# 04_-_CPU_-_DDR3_DDR3_MEM.net
KiCad netlist of a schematic drawn in Altium Designer
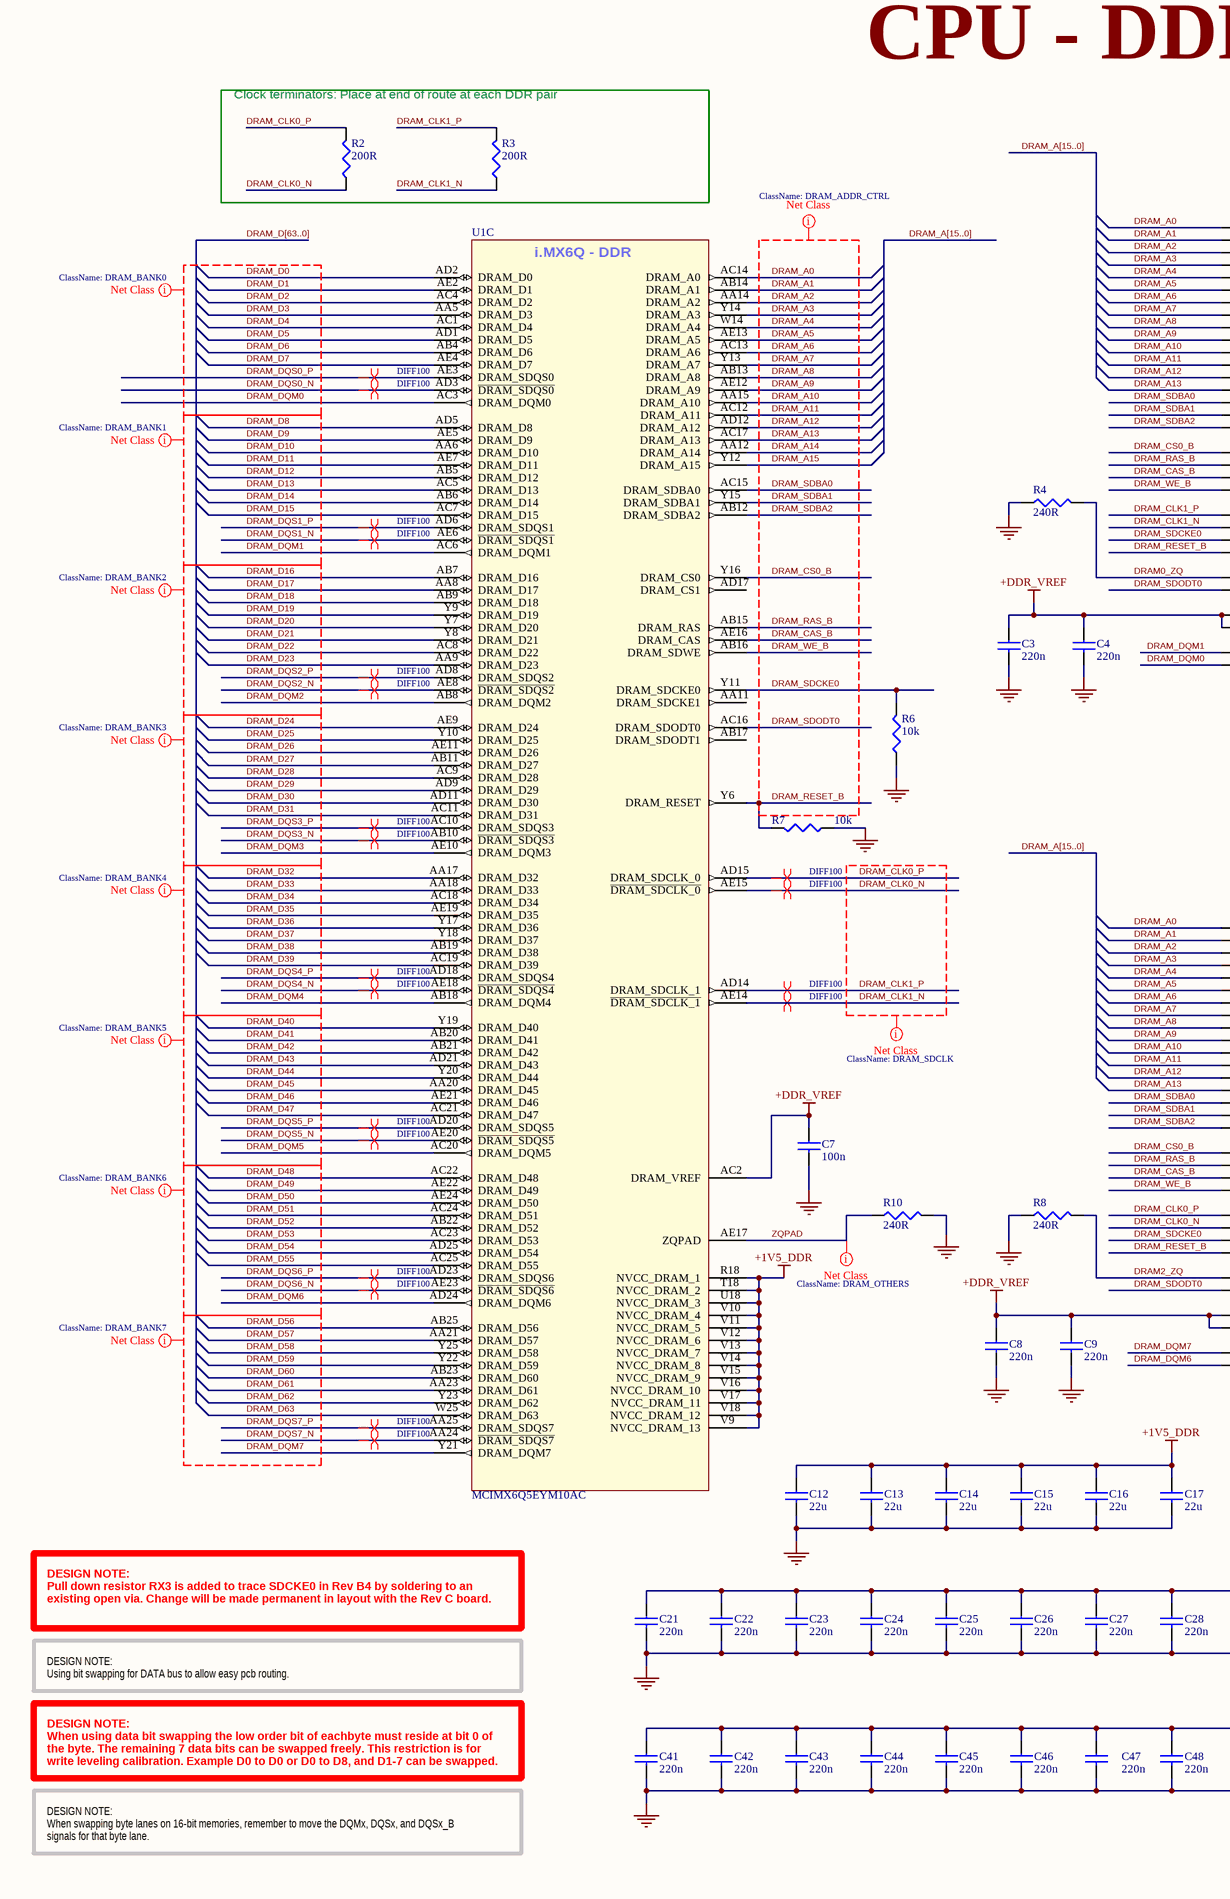
[diagram p0: [04] - CPU - DDR3, DDR3 MEM.SchDoc, left]
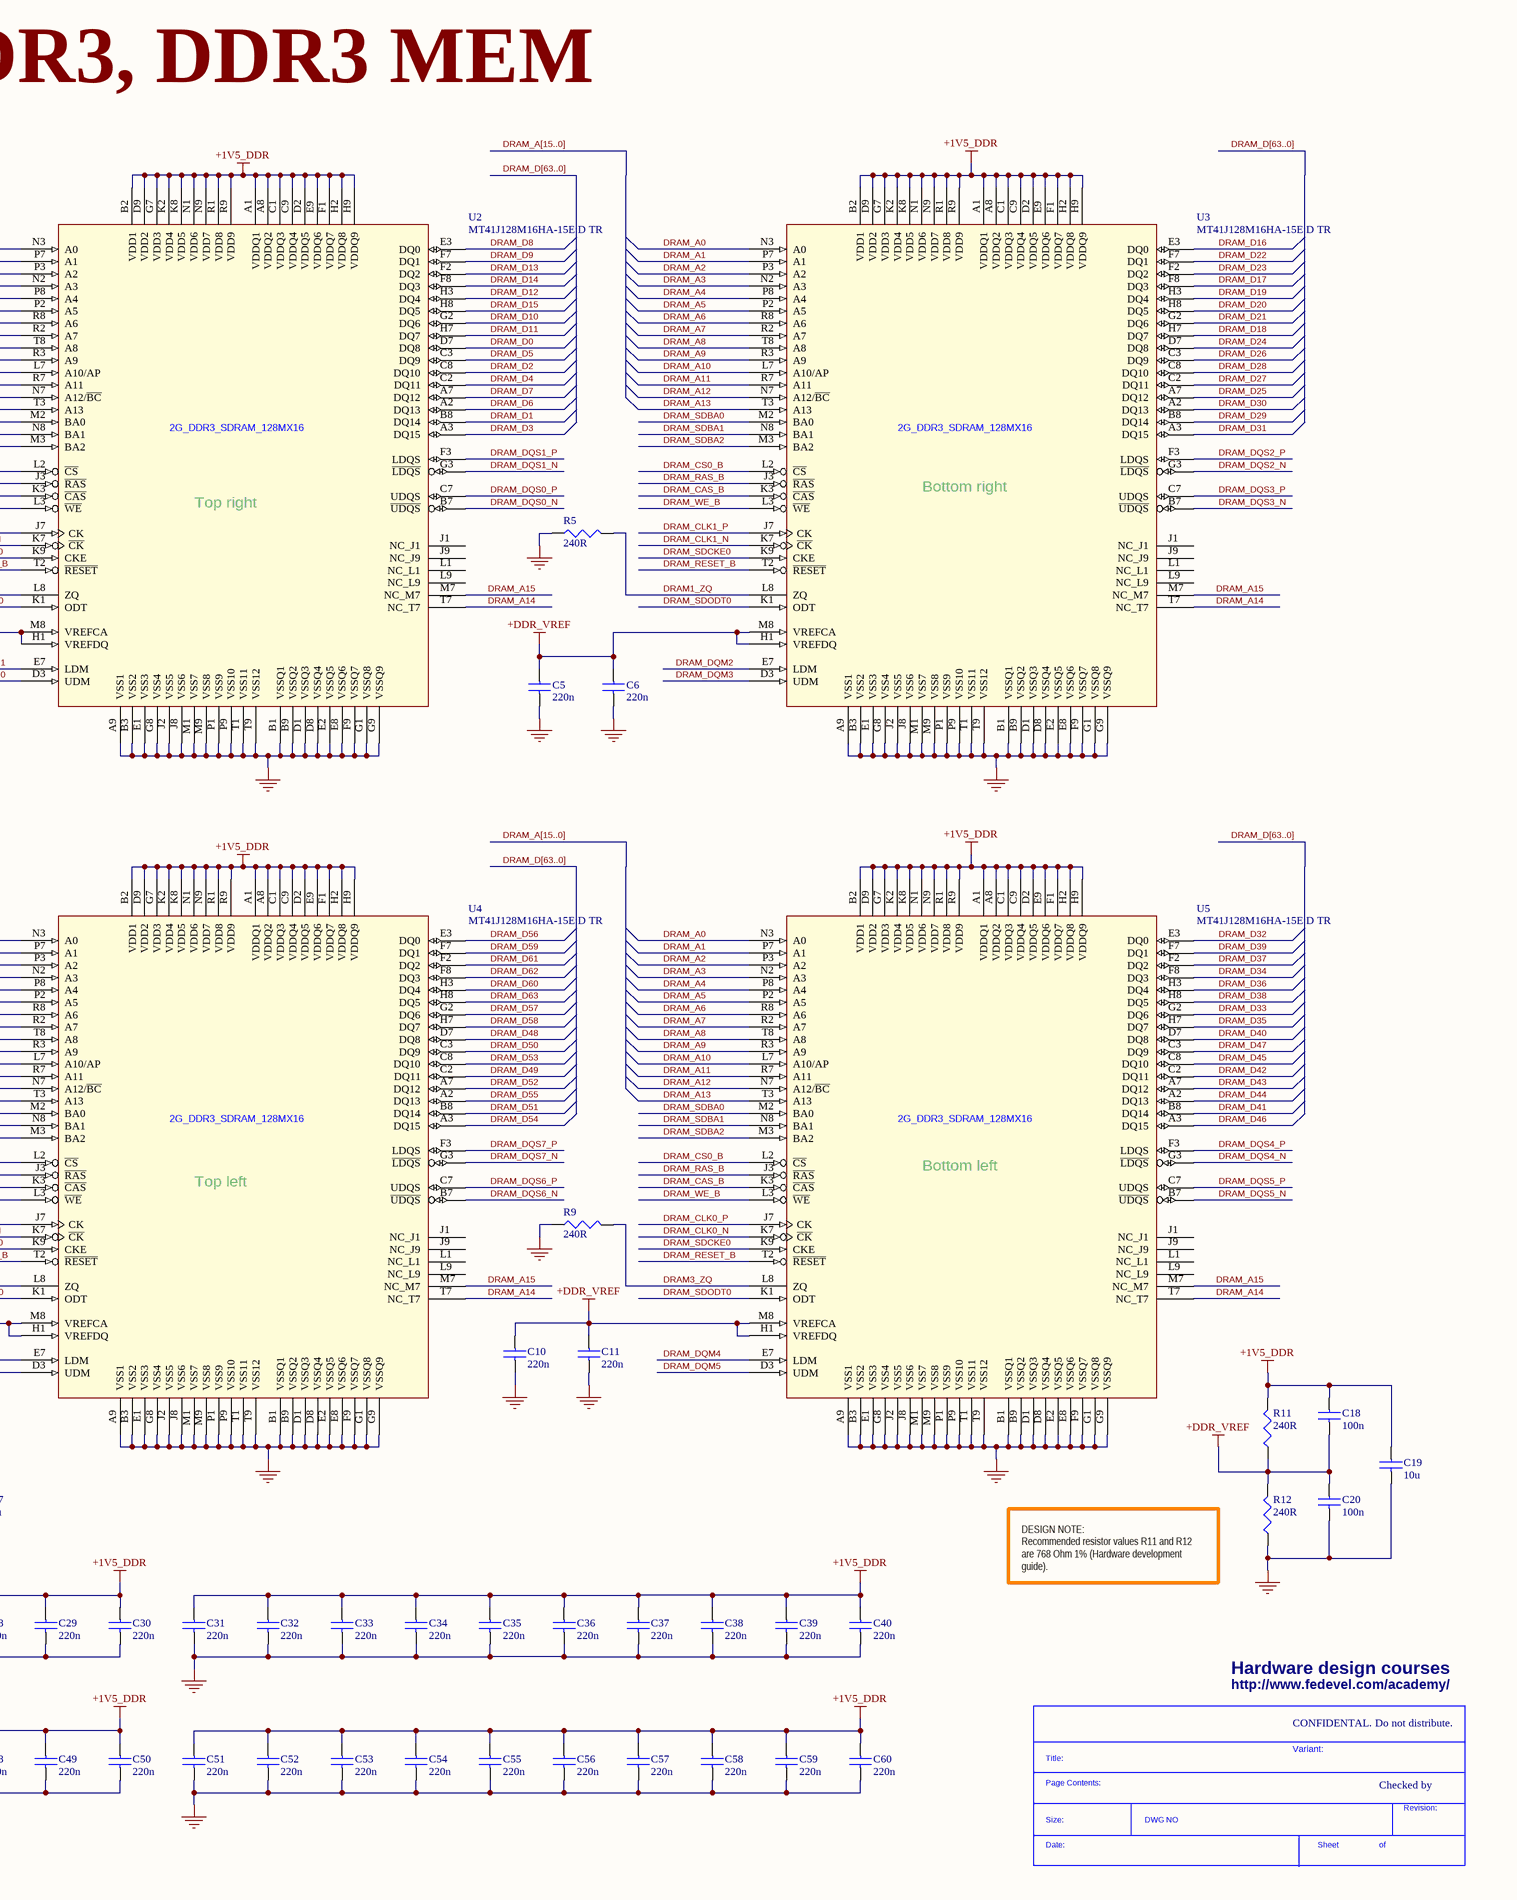
[diagram p1: [04] - CPU - DDR3, DDR3 MEM.SchDoc, right]

(export (version "E")
  (design (tool "Eeschema 10.0.6"))
  (components
    (comp (ref "C3")
      (value "220n")
      (footprint "C0402")
      (description "CAP CER .22UF 25V X5R 20% 0402")
      (fields
        (field (name "MANUFACTURER") "TDK Corporation")
        (field (name "MANUFACTURER PART NUMBER") "C1005X5R1E224M")
      )
      (libsource (lib "Integrated_Library_RF_FEB_2012") (part "C1005X5R1E224M"))
    )
    (comp (ref "C4")
      (value "220n")
      (footprint "C0402")
      (description "CAP CER .22UF 25V X5R 20% 0402")
      (fields
        (field (name "MANUFACTURER") "TDK Corporation")
        (field (name "MANUFACTURER PART NUMBER") "C1005X5R1E224M")
      )
      (libsource (lib "Integrated_Library_RF_FEB_2012") (part "C1005X5R1E224M"))
    )
    (comp (ref "C5")
      (value "220n")
      (footprint "C0402")
      (description "CAP CER .22UF 25V X5R 20% 0402")
      (fields
        (field (name "MANUFACTURER") "TDK Corporation")
        (field (name "MANUFACTURER PART NUMBER") "C1005X5R1E224M")
      )
      (libsource (lib "Integrated_Library_RF_FEB_2012") (part "C1005X5R1E224M"))
    )
    (comp (ref "C6")
      (value "220n")
      (footprint "C0402")
      (description "CAP CER .22UF 25V X5R 20% 0402")
      (fields
        (field (name "MANUFACTURER") "TDK Corporation")
        (field (name "MANUFACTURER PART NUMBER") "C1005X5R1E224M")
      )
      (libsource (lib "Integrated_Library_RF_FEB_2012") (part "C1005X5R1E224M"))
    )
    (comp (ref "C7")
      (value "100n")
      (footprint "C0402")
      (description "CAP CER .10UF 50V X5R 10% 0402")
      (fields
        (field (name "MANUFACTURER") "TDK Corporation")
        (field (name "MANUFACTURER PART NUMBER") "C1005X5R1H104K")
      )
      (libsource (lib "Integrated_Library_RF_FEB_2012") (part "C1005X5R1H104K"))
    )
    (comp (ref "C8")
      (value "220n")
      (footprint "C0402")
      (description "CAP CER .22UF 25V X5R 20% 0402")
      (fields
        (field (name "MANUFACTURER") "TDK Corporation")
        (field (name "MANUFACTURER PART NUMBER") "C1005X5R1E224M")
      )
      (libsource (lib "Integrated_Library_RF_FEB_2012") (part "C1005X5R1E224M"))
    )
    (comp (ref "C9")
      (value "220n")
      (footprint "C0402")
      (description "CAP CER .22UF 25V X5R 20% 0402")
      (fields
        (field (name "MANUFACTURER") "TDK Corporation")
        (field (name "MANUFACTURER PART NUMBER") "C1005X5R1E224M")
      )
      (libsource (lib "Integrated_Library_RF_FEB_2012") (part "C1005X5R1E224M"))
    )
    (comp (ref "C10")
      (value "220n")
      (footprint "C0402")
      (description "CAP CER .22UF 25V X5R 20% 0402")
      (fields
        (field (name "MANUFACTURER") "TDK Corporation")
        (field (name "MANUFACTURER PART NUMBER") "C1005X5R1E224M")
      )
      (libsource (lib "Integrated_Library_RF_FEB_2012") (part "C1005X5R1E224M"))
    )
    (comp (ref "C11")
      (value "220n")
      (footprint "C0402")
      (description "CAP CER .22UF 25V X5R 20% 0402")
      (fields
        (field (name "MANUFACTURER") "TDK Corporation")
        (field (name "MANUFACTURER PART NUMBER") "C1005X5R1E224M")
      )
      (libsource (lib "Integrated_Library_RF_FEB_2012") (part "C1005X5R1E224M"))
    )
    (comp (ref "C12")
      (value "22u")
      (footprint "C0603")
      (description "CAP CER 22UF 4V 20% X5R 0603")
      (fields
        (field (name "MANUFACTURER") "Murata Electronics North America")
        (field (name "MANUFACTURER PART NUMBER") "GRM188R60G226MEA0L")
        (field (name ".CHECKED PCB") "RF, used by MM")
        (field (name ".CHECKED SCH") "MM, checked by RF")
        (field (name ".CREATOR") "MM")
      )
      (libsource (lib "Schlib_RF") (part "GRM188R60G226MEA0L"))
    )
    (comp (ref "C13")
      (value "22u")
      (footprint "C0603")
      (description "CAP CER 22UF 4V 20% X5R 0603")
      (fields
        (field (name "MANUFACTURER") "Murata Electronics North America")
        (field (name "MANUFACTURER PART NUMBER") "GRM188R60G226MEA0L")
        (field (name ".CHECKED PCB") "RF, used by MM")
        (field (name ".CHECKED SCH") "MM, checked by RF")
        (field (name ".CREATOR") "MM")
      )
      (libsource (lib "Schlib_RF") (part "GRM188R60G226MEA0L"))
    )
    (comp (ref "C14")
      (value "22u")
      (footprint "C0603")
      (description "CAP CER 22UF 4V 20% X5R 0603")
      (fields
        (field (name "MANUFACTURER") "Murata Electronics North America")
        (field (name "MANUFACTURER PART NUMBER") "GRM188R60G226MEA0L")
        (field (name ".CHECKED PCB") "RF, used by MM")
        (field (name ".CHECKED SCH") "MM, checked by RF")
        (field (name ".CREATOR") "MM")
      )
      (libsource (lib "Schlib_RF") (part "GRM188R60G226MEA0L"))
    )
    (comp (ref "C15")
      (value "22u")
      (footprint "C0603")
      (description "CAP CER 22UF 4V 20% X5R 0603")
      (fields
        (field (name "MANUFACTURER") "Murata Electronics North America")
        (field (name "MANUFACTURER PART NUMBER") "GRM188R60G226MEA0L")
        (field (name ".CHECKED PCB") "RF, used by MM")
        (field (name ".CHECKED SCH") "MM, checked by RF")
        (field (name ".CREATOR") "MM")
      )
      (libsource (lib "Schlib_RF") (part "GRM188R60G226MEA0L"))
    )
    (comp (ref "C16")
      (value "22u")
      (footprint "C0603")
      (description "CAP CER 22UF 4V 20% X5R 0603")
      (fields
        (field (name "MANUFACTURER") "Murata Electronics North America")
        (field (name "MANUFACTURER PART NUMBER") "GRM188R60G226MEA0L")
        (field (name ".CHECKED PCB") "RF, used by MM")
        (field (name ".CHECKED SCH") "MM, checked by RF")
        (field (name ".CREATOR") "MM")
      )
      (libsource (lib "Schlib_RF") (part "GRM188R60G226MEA0L"))
    )
    (comp (ref "C17")
      (value "22u")
      (footprint "C0603")
      (description "CAP CER 22UF 4V 20% X5R 0603")
      (fields
        (field (name "MANUFACTURER") "Murata Electronics North America")
        (field (name "MANUFACTURER PART NUMBER") "GRM188R60G226MEA0L")
        (field (name ".CHECKED PCB") "RF, used by MM")
        (field (name ".CHECKED SCH") "MM, checked by RF")
        (field (name ".CREATOR") "MM")
      )
      (libsource (lib "Schlib_RF") (part "GRM188R60G226MEA0L"))
    )
    (comp (ref "C18")
      (value "100n")
      (footprint "C0402")
      (description "CAP CER .10UF 50V X5R 10% 0402")
      (fields
        (field (name "MANUFACTURER") "TDK Corporation")
        (field (name "MANUFACTURER PART NUMBER") "C1005X5R1H104K")
      )
      (libsource (lib "Integrated_Library_RF_FEB_2012") (part "C1005X5R1H104K"))
    )
    (comp (ref "C19")
      (value "10u")
      (footprint "C0603")
      (description "CAP CER 10UF 6.3V X5R 20% 0603")
      (fields
        (field (name "MANUFACTURER") "TDK Corporation")
        (field (name "MANUFACTURER PART NUMBER") "C1608X5R0J106M")
      )
      (libsource (lib "Integrated_Library_RF_FEB_2012") (part "C1608X5R0J106M"))
    )
    (comp (ref "C20")
      (value "100n")
      (footprint "C0402")
      (description "CAP CER .10UF 50V X5R 10% 0402")
      (fields
        (field (name "MANUFACTURER") "TDK Corporation")
        (field (name "MANUFACTURER PART NUMBER") "C1005X5R1H104K")
      )
      (libsource (lib "Integrated_Library_RF_FEB_2012") (part "C1005X5R1H104K"))
    )
    (comp (ref "C21")
      (value "220n")
      (footprint "C0402")
      (description "CAP CER .22UF 25V X5R 20% 0402")
      (fields
        (field (name "MANUFACTURER") "TDK Corporation")
        (field (name "MANUFACTURER PART NUMBER") "C1005X5R1E224M")
      )
      (libsource (lib "Integrated_Library_RF_FEB_2012") (part "C1005X5R1E224M"))
    )
    (comp (ref "C22")
      (value "220n")
      (footprint "C0402")
      (description "CAP CER .22UF 25V X5R 20% 0402")
      (fields
        (field (name "MANUFACTURER") "TDK Corporation")
        (field (name "MANUFACTURER PART NUMBER") "C1005X5R1E224M")
      )
      (libsource (lib "Integrated_Library_RF_FEB_2012") (part "C1005X5R1E224M"))
    )
    (comp (ref "C23")
      (value "220n")
      (footprint "C0402")
      (description "CAP CER .22UF 25V X5R 20% 0402")
      (fields
        (field (name "MANUFACTURER") "TDK Corporation")
        (field (name "MANUFACTURER PART NUMBER") "C1005X5R1E224M")
      )
      (libsource (lib "Integrated_Library_RF_FEB_2012") (part "C1005X5R1E224M"))
    )
    (comp (ref "C24")
      (value "220n")
      (footprint "C0402")
      (description "CAP CER .22UF 25V X5R 20% 0402")
      (fields
        (field (name "MANUFACTURER") "TDK Corporation")
        (field (name "MANUFACTURER PART NUMBER") "C1005X5R1E224M")
      )
      (libsource (lib "Integrated_Library_RF_FEB_2012") (part "C1005X5R1E224M"))
    )
    (comp (ref "C25")
      (value "220n")
      (footprint "C0402")
      (description "CAP CER .22UF 25V X5R 20% 0402")
      (fields
        (field (name "MANUFACTURER") "TDK Corporation")
        (field (name "MANUFACTURER PART NUMBER") "C1005X5R1E224M")
      )
      (libsource (lib "Integrated_Library_RF_FEB_2012") (part "C1005X5R1E224M"))
    )
    (comp (ref "C26")
      (value "220n")
      (footprint "C0402")
      (description "CAP CER .22UF 25V X5R 20% 0402")
      (fields
        (field (name "MANUFACTURER") "TDK Corporation")
        (field (name "MANUFACTURER PART NUMBER") "C1005X5R1E224M")
      )
      (libsource (lib "Integrated_Library_RF_FEB_2012") (part "C1005X5R1E224M"))
    )
    (comp (ref "C27")
      (value "220n")
      (footprint "C0402")
      (description "CAP CER .22UF 25V X5R 20% 0402")
      (fields
        (field (name "MANUFACTURER") "TDK Corporation")
        (field (name "MANUFACTURER PART NUMBER") "C1005X5R1E224M")
      )
      (libsource (lib "Integrated_Library_RF_FEB_2012") (part "C1005X5R1E224M"))
    )
    (comp (ref "C28")
      (value "220n")
      (footprint "C0402")
      (description "CAP CER .22UF 25V X5R 20% 0402")
      (fields
        (field (name "MANUFACTURER") "TDK Corporation")
        (field (name "MANUFACTURER PART NUMBER") "C1005X5R1E224M")
      )
      (libsource (lib "Integrated_Library_RF_FEB_2012") (part "C1005X5R1E224M"))
    )
    (comp (ref "C29")
      (value "220n")
      (footprint "C0402")
      (description "CAP CER .22UF 25V X5R 20% 0402")
      (fields
        (field (name "MANUFACTURER") "TDK Corporation")
        (field (name "MANUFACTURER PART NUMBER") "C1005X5R1E224M")
      )
      (libsource (lib "Integrated_Library_RF_FEB_2012") (part "C1005X5R1E224M"))
    )
    (comp (ref "C30")
      (value "220n")
      (footprint "C0402")
      (description "CAP CER .22UF 25V X5R 20% 0402")
      (fields
        (field (name "MANUFACTURER") "TDK Corporation")
        (field (name "MANUFACTURER PART NUMBER") "C1005X5R1E224M")
      )
      (libsource (lib "Integrated_Library_RF_FEB_2012") (part "C1005X5R1E224M"))
    )
    (comp (ref "C31")
      (value "220n")
      (footprint "C0402")
      (description "CAP CER .22UF 25V X5R 20% 0402")
      (fields
        (field (name "MANUFACTURER") "TDK Corporation")
        (field (name "MANUFACTURER PART NUMBER") "C1005X5R1E224M")
      )
      (libsource (lib "Integrated_Library_RF_FEB_2012") (part "C1005X5R1E224M"))
    )
    (comp (ref "C32")
      (value "220n")
      (footprint "C0402")
      (description "CAP CER .22UF 25V X5R 20% 0402")
      (fields
        (field (name "MANUFACTURER") "TDK Corporation")
        (field (name "MANUFACTURER PART NUMBER") "C1005X5R1E224M")
      )
      (libsource (lib "Integrated_Library_RF_FEB_2012") (part "C1005X5R1E224M"))
    )
    (comp (ref "C33")
      (value "220n")
      (footprint "C0402")
      (description "CAP CER .22UF 25V X5R 20% 0402")
      (fields
        (field (name "MANUFACTURER") "TDK Corporation")
        (field (name "MANUFACTURER PART NUMBER") "C1005X5R1E224M")
      )
      (libsource (lib "Integrated_Library_RF_FEB_2012") (part "C1005X5R1E224M"))
    )
    (comp (ref "C34")
      (value "220n")
      (footprint "C0402")
      (description "CAP CER .22UF 25V X5R 20% 0402")
      (fields
        (field (name "MANUFACTURER") "TDK Corporation")
        (field (name "MANUFACTURER PART NUMBER") "C1005X5R1E224M")
      )
      (libsource (lib "Integrated_Library_RF_FEB_2012") (part "C1005X5R1E224M"))
    )
    (comp (ref "C35")
      (value "220n")
      (footprint "C0402")
      (description "CAP CER .22UF 25V X5R 20% 0402")
      (fields
        (field (name "MANUFACTURER") "TDK Corporation")
        (field (name "MANUFACTURER PART NUMBER") "C1005X5R1E224M")
      )
      (libsource (lib "Integrated_Library_RF_FEB_2012") (part "C1005X5R1E224M"))
    )
    (comp (ref "C36")
      (value "220n")
      (footprint "C0402")
      (description "CAP CER .22UF 25V X5R 20% 0402")
      (fields
        (field (name "MANUFACTURER") "TDK Corporation")
        (field (name "MANUFACTURER PART NUMBER") "C1005X5R1E224M")
      )
      (libsource (lib "Integrated_Library_RF_FEB_2012") (part "C1005X5R1E224M"))
    )
    (comp (ref "C37")
      (value "220n")
      (footprint "C0402")
      (description "CAP CER .22UF 25V X5R 20% 0402")
      (fields
        (field (name "MANUFACTURER") "TDK Corporation")
        (field (name "MANUFACTURER PART NUMBER") "C1005X5R1E224M")
      )
      (libsource (lib "Integrated_Library_RF_FEB_2012") (part "C1005X5R1E224M"))
    )
    (comp (ref "C38")
      (value "220n")
      (footprint "C0402")
      (description "CAP CER .22UF 25V X5R 20% 0402")
      (fields
        (field (name "MANUFACTURER") "TDK Corporation")
        (field (name "MANUFACTURER PART NUMBER") "C1005X5R1E224M")
      )
      (libsource (lib "Integrated_Library_RF_FEB_2012") (part "C1005X5R1E224M"))
    )
    (comp (ref "C39")
      (value "220n")
      (footprint "C0402")
      (description "CAP CER .22UF 25V X5R 20% 0402")
      (fields
        (field (name "MANUFACTURER") "TDK Corporation")
        (field (name "MANUFACTURER PART NUMBER") "C1005X5R1E224M")
      )
      (libsource (lib "Integrated_Library_RF_FEB_2012") (part "C1005X5R1E224M"))
    )
    (comp (ref "C40")
      (value "220n")
      (footprint "C0402")
      (description "CAP CER .22UF 25V X5R 20% 0402")
      (fields
        (field (name "MANUFACTURER") "TDK Corporation")
        (field (name "MANUFACTURER PART NUMBER") "C1005X5R1E224M")
      )
      (libsource (lib "Integrated_Library_RF_FEB_2012") (part "C1005X5R1E224M"))
    )
    (comp (ref "C41")
      (value "220n")
      (footprint "C0402")
      (description "CAP CER .22UF 25V X5R 20% 0402")
      (fields
        (field (name "MANUFACTURER") "TDK Corporation")
        (field (name "MANUFACTURER PART NUMBER") "C1005X5R1E224M")
      )
      (libsource (lib "Integrated_Library_RF_FEB_2012") (part "C1005X5R1E224M"))
    )
    (comp (ref "C42")
      (value "220n")
      (footprint "C0402")
      (description "CAP CER .22UF 25V X5R 20% 0402")
      (fields
        (field (name "MANUFACTURER") "TDK Corporation")
        (field (name "MANUFACTURER PART NUMBER") "C1005X5R1E224M")
      )
      (libsource (lib "Integrated_Library_RF_FEB_2012") (part "C1005X5R1E224M"))
    )
    (comp (ref "C43")
      (value "220n")
      (footprint "C0402")
      (description "CAP CER .22UF 25V X5R 20% 0402")
      (fields
        (field (name "MANUFACTURER") "TDK Corporation")
        (field (name "MANUFACTURER PART NUMBER") "C1005X5R1E224M")
      )
      (libsource (lib "Integrated_Library_RF_FEB_2012") (part "C1005X5R1E224M"))
    )
    (comp (ref "C44")
      (value "220n")
      (footprint "C0402")
      (description "CAP CER .22UF 25V X5R 20% 0402")
      (fields
        (field (name "MANUFACTURER") "TDK Corporation")
        (field (name "MANUFACTURER PART NUMBER") "C1005X5R1E224M")
      )
      (libsource (lib "Integrated_Library_RF_FEB_2012") (part "C1005X5R1E224M"))
    )
    (comp (ref "C45")
      (value "220n")
      (footprint "C0402")
      (description "CAP CER .22UF 25V X5R 20% 0402")
      (fields
        (field (name "MANUFACTURER") "TDK Corporation")
        (field (name "MANUFACTURER PART NUMBER") "C1005X5R1E224M")
      )
      (libsource (lib "Integrated_Library_RF_FEB_2012") (part "C1005X5R1E224M"))
    )
    (comp (ref "C46")
      (value "220n")
      (footprint "C0402")
      (description "CAP CER .22UF 25V X5R 20% 0402")
      (fields
        (field (name "MANUFACTURER") "TDK Corporation")
        (field (name "MANUFACTURER PART NUMBER") "C1005X5R1E224M")
      )
      (libsource (lib "Integrated_Library_RF_FEB_2012") (part "C1005X5R1E224M"))
    )
    (comp (ref "C47")
      (value "220n")
      (footprint "C0402")
      (description "CAP CER .22UF 25V X5R 20% 0402")
      (fields
        (field (name "MANUFACTURER") "TDK Corporation")
        (field (name "MANUFACTURER PART NUMBER") "C1005X5R1E224M")
      )
      (libsource (lib "Integrated_Library_RF_FEB_2012") (part "C1005X5R1E224M"))
    )
    (comp (ref "C48")
      (value "220n")
      (footprint "C0402")
      (description "CAP CER .22UF 25V X5R 20% 0402")
      (fields
        (field (name "MANUFACTURER") "TDK Corporation")
        (field (name "MANUFACTURER PART NUMBER") "C1005X5R1E224M")
      )
      (libsource (lib "Integrated_Library_RF_FEB_2012") (part "C1005X5R1E224M"))
    )
    (comp (ref "C49")
      (value "220n")
      (footprint "C0402")
      (description "CAP CER .22UF 25V X5R 20% 0402")
      (fields
        (field (name "MANUFACTURER") "TDK Corporation")
        (field (name "MANUFACTURER PART NUMBER") "C1005X5R1E224M")
      )
      (libsource (lib "Integrated_Library_RF_FEB_2012") (part "C1005X5R1E224M"))
    )
    (comp (ref "C50")
      (value "220n")
      (footprint "C0402")
      (description "CAP CER .22UF 25V X5R 20% 0402")
      (fields
        (field (name "MANUFACTURER") "TDK Corporation")
        (field (name "MANUFACTURER PART NUMBER") "C1005X5R1E224M")
      )
      (libsource (lib "Integrated_Library_RF_FEB_2012") (part "C1005X5R1E224M"))
    )
    (comp (ref "C51")
      (value "220n")
      (footprint "C0402")
      (description "CAP CER .22UF 25V X5R 20% 0402")
      (fields
        (field (name "MANUFACTURER") "TDK Corporation")
        (field (name "MANUFACTURER PART NUMBER") "C1005X5R1E224M")
      )
      (libsource (lib "Integrated_Library_RF_FEB_2012") (part "C1005X5R1E224M"))
    )
    (comp (ref "C52")
      (value "220n")
      (footprint "C0402")
      (description "CAP CER .22UF 25V X5R 20% 0402")
      (fields
        (field (name "MANUFACTURER") "TDK Corporation")
        (field (name "MANUFACTURER PART NUMBER") "C1005X5R1E224M")
      )
      (libsource (lib "Integrated_Library_RF_FEB_2012") (part "C1005X5R1E224M"))
    )
    (comp (ref "C53")
      (value "220n")
      (footprint "C0402")
      (description "CAP CER .22UF 25V X5R 20% 0402")
      (fields
        (field (name "MANUFACTURER") "TDK Corporation")
        (field (name "MANUFACTURER PART NUMBER") "C1005X5R1E224M")
      )
      (libsource (lib "Integrated_Library_RF_FEB_2012") (part "C1005X5R1E224M"))
    )
    (comp (ref "C54")
      (value "220n")
      (footprint "C0402")
      (description "CAP CER .22UF 25V X5R 20% 0402")
      (fields
        (field (name "MANUFACTURER") "TDK Corporation")
        (field (name "MANUFACTURER PART NUMBER") "C1005X5R1E224M")
      )
      (libsource (lib "Integrated_Library_RF_FEB_2012") (part "C1005X5R1E224M"))
    )
    (comp (ref "C55")
      (value "220n")
      (footprint "C0402")
      (description "CAP CER .22UF 25V X5R 20% 0402")
      (fields
        (field (name "MANUFACTURER") "TDK Corporation")
        (field (name "MANUFACTURER PART NUMBER") "C1005X5R1E224M")
      )
      (libsource (lib "Integrated_Library_RF_FEB_2012") (part "C1005X5R1E224M"))
    )
    (comp (ref "C56")
      (value "220n")
      (footprint "C0402")
      (description "CAP CER .22UF 25V X5R 20% 0402")
      (fields
        (field (name "MANUFACTURER") "TDK Corporation")
        (field (name "MANUFACTURER PART NUMBER") "C1005X5R1E224M")
      )
      (libsource (lib "Integrated_Library_RF_FEB_2012") (part "C1005X5R1E224M"))
    )
    (comp (ref "C57")
      (value "220n")
      (footprint "C0402")
      (description "CAP CER .22UF 25V X5R 20% 0402")
      (fields
        (field (name "MANUFACTURER") "TDK Corporation")
        (field (name "MANUFACTURER PART NUMBER") "C1005X5R1E224M")
      )
      (libsource (lib "Integrated_Library_RF_FEB_2012") (part "C1005X5R1E224M"))
    )
    (comp (ref "C58")
      (value "220n")
      (footprint "C0402")
      (description "CAP CER .22UF 25V X5R 20% 0402")
      (fields
        (field (name "MANUFACTURER") "TDK Corporation")
        (field (name "MANUFACTURER PART NUMBER") "C1005X5R1E224M")
      )
      (libsource (lib "Integrated_Library_RF_FEB_2012") (part "C1005X5R1E224M"))
    )
    (comp (ref "C59")
      (value "220n")
      (footprint "C0402")
      (description "CAP CER .22UF 25V X5R 20% 0402")
      (fields
        (field (name "MANUFACTURER") "TDK Corporation")
        (field (name "MANUFACTURER PART NUMBER") "C1005X5R1E224M")
      )
      (libsource (lib "Integrated_Library_RF_FEB_2012") (part "C1005X5R1E224M"))
    )
    (comp (ref "C60")
      (value "220n")
      (footprint "C0402")
      (description "CAP CER .22UF 25V X5R 20% 0402")
      (fields
        (field (name "MANUFACTURER") "TDK Corporation")
        (field (name "MANUFACTURER PART NUMBER") "C1005X5R1E224M")
      )
      (libsource (lib "Integrated_Library_RF_FEB_2012") (part "C1005X5R1E224M"))
    )
    (comp (ref "R2")
      (value "200R")
      (footprint "R0402")
      (description "RES 200 OHM 1/16W 1% 0402 SMD")
      (fields
        (field (name "MANUFACTURER") "Vishay Dale")
        (field (name "MANUFACTURER PART NUMBER") "CRCW0402200RFKED")
        (field (name ".CHECKED PCB") "RF, used by MM")
        (field (name ".CHECKED SCH") "MM, checked by RF")
        (field (name ".CREATOR") "MM")
      )
      (libsource (lib "Schlib_RF") (part "CRCW0402200RFKED"))
    )
    (comp (ref "R3")
      (value "200R")
      (footprint "R0402")
      (description "RES 200 OHM 1/16W 1% 0402 SMD")
      (fields
        (field (name "MANUFACTURER") "Vishay Dale")
        (field (name "MANUFACTURER PART NUMBER") "CRCW0402200RFKED")
        (field (name ".CHECKED PCB") "RF, used by MM")
        (field (name ".CHECKED SCH") "MM, checked by RF")
        (field (name ".CREATOR") "MM")
      )
      (libsource (lib "Schlib_RF") (part "CRCW0402200RFKED"))
    )
    (comp (ref "R4")
      (value "240R")
      (footprint "R0402")
      (description "RES TF 240 OHM 1% 0.0625W 0402")
      (fields
        (field (name "MANUFACTURER") "Stackpole Electronics Inc")
        (field (name "MANUFACTURER PART NUMBER") "RMCF0402FT240R")
      )
      (libsource (lib "Integrated_Library_RF_FEB_2012") (part "RMCF0402FT240R"))
    )
    (comp (ref "R5")
      (value "240R")
      (footprint "R0402")
      (description "RES TF 240 OHM 1% 0.0625W 0402")
      (fields
        (field (name "MANUFACTURER") "Stackpole Electronics Inc")
        (field (name "MANUFACTURER PART NUMBER") "RMCF0402FT240R")
      )
      (libsource (lib "Integrated_Library_RF_FEB_2012") (part "RMCF0402FT240R"))
    )
    (comp (ref "R6")
      (value "10k")
      (footprint "R0402")
      (description "RES 10.0K OHM 1/16W 1% 0402 SMD")
      (fields
        (field (name "MANUFACTURER") "Yageo")
        (field (name "MANUFACTURER PART NUMBER") "RC0402FR-0710KL")
      )
      (libsource (lib "Integrated_Library_RF_FEB_2012") (part "RC0402FR-0710KL"))
    )
    (comp (ref "R7")
      (value "10k")
      (footprint "R0402")
      (description "RES 10.0K OHM 1/16W 1% 0402 SMD")
      (fields
        (field (name "MANUFACTURER") "Yageo")
        (field (name "MANUFACTURER PART NUMBER") "RC0402FR-0710KL")
      )
      (libsource (lib "Integrated_Library_RF_FEB_2012") (part "RC0402FR-0710KL"))
    )
    (comp (ref "R8")
      (value "240R")
      (footprint "R0402")
      (description "RES TF 240 OHM 1% 0.0625W 0402")
      (fields
        (field (name "MANUFACTURER") "Stackpole Electronics Inc")
        (field (name "MANUFACTURER PART NUMBER") "RMCF0402FT240R")
      )
      (libsource (lib "Integrated_Library_RF_FEB_2012") (part "RMCF0402FT240R"))
    )
    (comp (ref "R9")
      (value "240R")
      (footprint "R0402")
      (description "RES TF 240 OHM 1% 0.0625W 0402")
      (fields
        (field (name "MANUFACTURER") "Stackpole Electronics Inc")
        (field (name "MANUFACTURER PART NUMBER") "RMCF0402FT240R")
      )
      (libsource (lib "Integrated_Library_RF_FEB_2012") (part "RMCF0402FT240R"))
    )
    (comp (ref "R10")
      (value "240R")
      (footprint "R0402")
      (description "RES TF 240 OHM 1% 0.0625W 0402")
      (fields
        (field (name "MANUFACTURER") "Stackpole Electronics Inc")
        (field (name "MANUFACTURER PART NUMBER") "RMCF0402FT240R")
      )
      (libsource (lib "Integrated_Library_RF_FEB_2012") (part "RMCF0402FT240R"))
    )
    (comp (ref "R11")
      (value "240R")
      (footprint "R0402")
      (description "RES TF 240 OHM 1% 0.0625W 0402")
      (fields
        (field (name "MANUFACTURER") "Stackpole Electronics Inc")
        (field (name "MANUFACTURER PART NUMBER") "RMCF0402FT240R")
      )
      (libsource (lib "Integrated_Library_RF_FEB_2012") (part "RMCF0402FT240R"))
    )
    (comp (ref "R12")
      (value "240R")
      (footprint "R0402")
      (description "RES TF 240 OHM 1% 0.0625W 0402")
      (fields
        (field (name "MANUFACTURER") "Stackpole Electronics Inc")
        (field (name "MANUFACTURER PART NUMBER") "RMCF0402FT240R")
      )
      (libsource (lib "Integrated_Library_RF_FEB_2012") (part "RMCF0402FT240R"))
    )
    (comp (ref "U1")
      (value "MCIMX6Q5EYM10AC")
      (footprint "PBGA624")
      (description "IC MCU 32BIT ARM QUAD 624FCBGA")
      (fields
        (field (name "MANUFACTURER") "Freescale Semiconductor")
        (field (name ".CREATOR") "MM")
        (field (name ".CHECKED PCB") "MM, checked by RF")
        (field (name ".CHECKED SCH") "MM")
      )
      (libsource (lib "Schlib_RF") (part "MCIMX6Q5EYM10AC"))
    )
    (comp (ref "U2")
      (value "MT41J128M16HA-15E:D TR")
      (footprint "96_FPGA_DD3")
      (description "IC DDR3 SDRAM 2GBIT 667MHZ 96BGA")
      (fields
        (field (name "MANUFACTURER") "Micron Technology Inc")
        (field (name ".CREATOR") "MM")
        (field (name ".CHECKED PCB") "RF, used by MM")
        (field (name ".CHECKED SCH") "MM, checked by RF")
      )
      (libsource (lib "Schlib_RF") (part "MT41J128M16HA-15E{colon}D TR"))
    )
    (comp (ref "U3")
      (value "MT41J128M16HA-15E:D TR")
      (footprint "96_FPGA_DD3")
      (description "IC DDR3 SDRAM 2GBIT 667MHZ 96BGA")
      (fields
        (field (name "MANUFACTURER") "Micron Technology Inc")
        (field (name ".CREATOR") "MM")
        (field (name ".CHECKED PCB") "RF, used by MM")
        (field (name ".CHECKED SCH") "MM, checked by RF")
      )
      (libsource (lib "Schlib_RF") (part "MT41J128M16HA-15E{colon}D TR"))
    )
    (comp (ref "U4")
      (value "MT41J128M16HA-15E:D TR")
      (footprint "96_FPGA_DD3")
      (description "IC DDR3 SDRAM 2GBIT 667MHZ 96BGA")
      (fields
        (field (name "MANUFACTURER") "Micron Technology Inc")
        (field (name ".CREATOR") "MM")
        (field (name ".CHECKED PCB") "RF, used by MM")
        (field (name ".CHECKED SCH") "MM, checked by RF")
      )
      (libsource (lib "Schlib_RF") (part "MT41J128M16HA-15E{colon}D TR"))
    )
    (comp (ref "U5")
      (value "MT41J128M16HA-15E:D TR")
      (footprint "96_FPGA_DD3")
      (description "IC DDR3 SDRAM 2GBIT 667MHZ 96BGA")
      (fields
        (field (name "MANUFACTURER") "Micron Technology Inc")
        (field (name ".CREATOR") "MM")
        (field (name ".CHECKED PCB") "RF, used by MM")
        (field (name ".CHECKED SCH") "MM, checked by RF")
      )
      (libsource (lib "Schlib_RF") (part "MT41J128M16HA-15E{colon}D TR"))
    )
  )
  (nets
    (net (code "1") (name "+1V5_DDR") (class "Default")
      (node (ref "C12") (pin "1") (pinfunction "1_1") (pintype "passive"))
      (node (ref "C13") (pin "1") (pinfunction "1_1") (pintype "passive"))
      (node (ref "C14") (pin "1") (pinfunction "1_1") (pintype "passive"))
      (node (ref "C15") (pin "1") (pinfunction "1_1") (pintype "passive"))
      (node (ref "C16") (pin "1") (pinfunction "1_1") (pintype "passive"))
      (node (ref "C17") (pin "1") (pinfunction "1_1") (pintype "passive"))
      (node (ref "C18") (pin "1") (pinfunction "1_1") (pintype "passive"))
      (node (ref "C19") (pin "1") (pinfunction "1_1") (pintype "passive"))
      (node (ref "C21") (pin "1") (pinfunction "1_1") (pintype "passive"))
      (node (ref "C22") (pin "1") (pinfunction "1_1") (pintype "passive"))
      (node (ref "C23") (pin "1") (pinfunction "1_1") (pintype "passive"))
      (node (ref "C24") (pin "1") (pinfunction "1_1") (pintype "passive"))
      (node (ref "C25") (pin "1") (pinfunction "1_1") (pintype "passive"))
      (node (ref "C26") (pin "1") (pinfunction "1_1") (pintype "passive"))
      (node (ref "C27") (pin "1") (pinfunction "1_1") (pintype "passive"))
      (node (ref "C28") (pin "1") (pinfunction "1_1") (pintype "passive"))
      (node (ref "C29") (pin "1") (pinfunction "1_1") (pintype "passive"))
      (node (ref "C30") (pin "1") (pinfunction "1_1") (pintype "passive"))
      (node (ref "C31") (pin "1") (pinfunction "1_1") (pintype "passive"))
      (node (ref "C32") (pin "1") (pinfunction "1_1") (pintype "passive"))
      (node (ref "C33") (pin "1") (pinfunction "1_1") (pintype "passive"))
      (node (ref "C34") (pin "1") (pinfunction "1_1") (pintype "passive"))
      (node (ref "C35") (pin "1") (pinfunction "1_1") (pintype "passive"))
      (node (ref "C36") (pin "1") (pinfunction "1_1") (pintype "passive"))
      (node (ref "C37") (pin "1") (pinfunction "1_1") (pintype "passive"))
      (node (ref "C38") (pin "1") (pinfunction "1_1") (pintype "passive"))
      (node (ref "C39") (pin "1") (pinfunction "1_1") (pintype "passive"))
      (node (ref "C40") (pin "1") (pinfunction "1_1") (pintype "passive"))
      (node (ref "C41") (pin "1") (pinfunction "1_1") (pintype "passive"))
      (node (ref "C42") (pin "1") (pinfunction "1_1") (pintype "passive"))
      (node (ref "C43") (pin "1") (pinfunction "1_1") (pintype "passive"))
      (node (ref "C44") (pin "1") (pinfunction "1_1") (pintype "passive"))
      (node (ref "C45") (pin "1") (pinfunction "1_1") (pintype "passive"))
      (node (ref "C46") (pin "1") (pinfunction "1_1") (pintype "passive"))
      (node (ref "C47") (pin "1") (pinfunction "1_1") (pintype "passive"))
      (node (ref "C48") (pin "1") (pinfunction "1_1") (pintype "passive"))
      (node (ref "C49") (pin "1") (pinfunction "1_1") (pintype "passive"))
      (node (ref "C50") (pin "1") (pinfunction "1_1") (pintype "passive"))
      (node (ref "C51") (pin "1") (pinfunction "1_1") (pintype "passive"))
      (node (ref "C52") (pin "1") (pinfunction "1_1") (pintype "passive"))
      (node (ref "C53") (pin "1") (pinfunction "1_1") (pintype "passive"))
      (node (ref "C54") (pin "1") (pinfunction "1_1") (pintype "passive"))
      (node (ref "C55") (pin "1") (pinfunction "1_1") (pintype "passive"))
      (node (ref "C56") (pin "1") (pinfunction "1_1") (pintype "passive"))
      (node (ref "C57") (pin "1") (pinfunction "1_1") (pintype "passive"))
      (node (ref "C58") (pin "1") (pinfunction "1_1") (pintype "passive"))
      (node (ref "C59") (pin "1") (pinfunction "1_1") (pintype "passive"))
      (node (ref "C60") (pin "1") (pinfunction "1_1") (pintype "passive"))
      (node (ref "R11") (pin "2") (pinfunction "2_2") (pintype "passive"))
      (node (ref "U1") (pin "R18") (pinfunction "NVCC_DRAM_1_R18") (pintype "power_in"))
      (node (ref "U1") (pin "T18") (pinfunction "NVCC_DRAM_2_T18") (pintype "power_in"))
      (node (ref "U1") (pin "U18") (pinfunction "NVCC_DRAM_3_U18") (pintype "power_in"))
      (node (ref "U1") (pin "V10") (pinfunction "NVCC_DRAM_4_V10") (pintype "power_in"))
      (node (ref "U1") (pin "V11") (pinfunction "NVCC_DRAM_5_V11") (pintype "power_in"))
      (node (ref "U1") (pin "V12") (pinfunction "NVCC_DRAM_6_V12") (pintype "power_in"))
      (node (ref "U1") (pin "V13") (pinfunction "NVCC_DRAM_7_V13") (pintype "power_in"))
      (node (ref "U1") (pin "V14") (pinfunction "NVCC_DRAM_8_V14") (pintype "power_in"))
      (node (ref "U1") (pin "V15") (pinfunction "NVCC_DRAM_9_V15") (pintype "power_in"))
      (node (ref "U1") (pin "V16") (pinfunction "NVCC_DRAM_10_V16") (pintype "power_in"))
      (node (ref "U1") (pin "V17") (pinfunction "NVCC_DRAM_11_V17") (pintype "power_in"))
      (node (ref "U1") (pin "V18") (pinfunction "NVCC_DRAM_12_V18") (pintype "power_in"))
      (node (ref "U1") (pin "V9") (pinfunction "NVCC_DRAM_13_V9") (pintype "power_in"))
      (node (ref "U2") (pin "A1") (pinfunction "VDDQ1_A1") (pintype "power_in"))
      (node (ref "U2") (pin "A8") (pinfunction "VDDQ2_A8") (pintype "power_in"))
      (node (ref "U2") (pin "B2") (pinfunction "VDD1_B2") (pintype "power_in"))
      (node (ref "U2") (pin "C1") (pinfunction "VDDQ3_C1") (pintype "power_in"))
      (node (ref "U2") (pin "C9") (pinfunction "VDDQ4_C9") (pintype "power_in"))
      (node (ref "U2") (pin "D2") (pinfunction "VDDQ5_D2") (pintype "power_in"))
      (node (ref "U2") (pin "D9") (pinfunction "VDD2_D9") (pintype "power_in"))
      (node (ref "U2") (pin "E9") (pinfunction "VDDQ6_E9") (pintype "power_in"))
      (node (ref "U2") (pin "F1") (pinfunction "VDDQ7_F1") (pintype "power_in"))
      (node (ref "U2") (pin "G7") (pinfunction "VDD3_G7") (pintype "power_in"))
      (node (ref "U2") (pin "H2") (pinfunction "VDDQ8_H2") (pintype "power_in"))
      (node (ref "U2") (pin "H9") (pinfunction "VDDQ9_H9") (pintype "power_in"))
      (node (ref "U2") (pin "K2") (pinfunction "VDD4_K2") (pintype "power_in"))
      (node (ref "U2") (pin "K8") (pinfunction "VDD5_K8") (pintype "power_in"))
      (node (ref "U2") (pin "N1") (pinfunction "VDD6_N1") (pintype "power_in"))
      (node (ref "U2") (pin "N9") (pinfunction "VDD7_N9") (pintype "power_in"))
      (node (ref "U2") (pin "R1") (pinfunction "VDD8_R1") (pintype "power_in"))
      (node (ref "U2") (pin "R9") (pinfunction "VDD9_R9") (pintype "power_in"))
      (node (ref "U3") (pin "A1") (pinfunction "VDDQ1_A1") (pintype "power_in"))
      (node (ref "U3") (pin "A8") (pinfunction "VDDQ2_A8") (pintype "power_in"))
      (node (ref "U3") (pin "B2") (pinfunction "VDD1_B2") (pintype "power_in"))
      (node (ref "U3") (pin "C1") (pinfunction "VDDQ3_C1") (pintype "power_in"))
      (node (ref "U3") (pin "C9") (pinfunction "VDDQ4_C9") (pintype "power_in"))
      (node (ref "U3") (pin "D2") (pinfunction "VDDQ5_D2") (pintype "power_in"))
      (node (ref "U3") (pin "D9") (pinfunction "VDD2_D9") (pintype "power_in"))
      (node (ref "U3") (pin "E9") (pinfunction "VDDQ6_E9") (pintype "power_in"))
      (node (ref "U3") (pin "F1") (pinfunction "VDDQ7_F1") (pintype "power_in"))
      (node (ref "U3") (pin "G7") (pinfunction "VDD3_G7") (pintype "power_in"))
      (node (ref "U3") (pin "H2") (pinfunction "VDDQ8_H2") (pintype "power_in"))
      (node (ref "U3") (pin "H9") (pinfunction "VDDQ9_H9") (pintype "power_in"))
      (node (ref "U3") (pin "K2") (pinfunction "VDD4_K2") (pintype "power_in"))
      (node (ref "U3") (pin "K8") (pinfunction "VDD5_K8") (pintype "power_in"))
      (node (ref "U3") (pin "N1") (pinfunction "VDD6_N1") (pintype "power_in"))
      (node (ref "U3") (pin "N9") (pinfunction "VDD7_N9") (pintype "power_in"))
      (node (ref "U3") (pin "R1") (pinfunction "VDD8_R1") (pintype "power_in"))
      (node (ref "U3") (pin "R9") (pinfunction "VDD9_R9") (pintype "power_in"))
      (node (ref "U4") (pin "A1") (pinfunction "VDDQ1_A1") (pintype "power_in"))
      (node (ref "U4") (pin "A8") (pinfunction "VDDQ2_A8") (pintype "power_in"))
      (node (ref "U4") (pin "B2") (pinfunction "VDD1_B2") (pintype "power_in"))
      (node (ref "U4") (pin "C1") (pinfunction "VDDQ3_C1") (pintype "power_in"))
      (node (ref "U4") (pin "C9") (pinfunction "VDDQ4_C9") (pintype "power_in"))
      (node (ref "U4") (pin "D2") (pinfunction "VDDQ5_D2") (pintype "power_in"))
      (node (ref "U4") (pin "D9") (pinfunction "VDD2_D9") (pintype "power_in"))
      (node (ref "U4") (pin "E9") (pinfunction "VDDQ6_E9") (pintype "power_in"))
      (node (ref "U4") (pin "F1") (pinfunction "VDDQ7_F1") (pintype "power_in"))
      (node (ref "U4") (pin "G7") (pinfunction "VDD3_G7") (pintype "power_in"))
      (node (ref "U4") (pin "H2") (pinfunction "VDDQ8_H2") (pintype "power_in"))
      (node (ref "U4") (pin "H9") (pinfunction "VDDQ9_H9") (pintype "power_in"))
      (node (ref "U4") (pin "K2") (pinfunction "VDD4_K2") (pintype "power_in"))
      (node (ref "U4") (pin "K8") (pinfunction "VDD5_K8") (pintype "power_in"))
      (node (ref "U4") (pin "N1") (pinfunction "VDD6_N1") (pintype "power_in"))
      (node (ref "U4") (pin "N9") (pinfunction "VDD7_N9") (pintype "power_in"))
      (node (ref "U4") (pin "R1") (pinfunction "VDD8_R1") (pintype "power_in"))
      (node (ref "U4") (pin "R9") (pinfunction "VDD9_R9") (pintype "power_in"))
      (node (ref "U5") (pin "A1") (pinfunction "VDDQ1_A1") (pintype "power_in"))
      (node (ref "U5") (pin "A8") (pinfunction "VDDQ2_A8") (pintype "power_in"))
      (node (ref "U5") (pin "B2") (pinfunction "VDD1_B2") (pintype "power_in"))
      (node (ref "U5") (pin "C1") (pinfunction "VDDQ3_C1") (pintype "power_in"))
      (node (ref "U5") (pin "C9") (pinfunction "VDDQ4_C9") (pintype "power_in"))
      (node (ref "U5") (pin "D2") (pinfunction "VDDQ5_D2") (pintype "power_in"))
      (node (ref "U5") (pin "D9") (pinfunction "VDD2_D9") (pintype "power_in"))
      (node (ref "U5") (pin "E9") (pinfunction "VDDQ6_E9") (pintype "power_in"))
      (node (ref "U5") (pin "F1") (pinfunction "VDDQ7_F1") (pintype "power_in"))
      (node (ref "U5") (pin "G7") (pinfunction "VDD3_G7") (pintype "power_in"))
      (node (ref "U5") (pin "H2") (pinfunction "VDDQ8_H2") (pintype "power_in"))
      (node (ref "U5") (pin "H9") (pinfunction "VDDQ9_H9") (pintype "power_in"))
      (node (ref "U5") (pin "K2") (pinfunction "VDD4_K2") (pintype "power_in"))
      (node (ref "U5") (pin "K8") (pinfunction "VDD5_K8") (pintype "power_in"))
      (node (ref "U5") (pin "N1") (pinfunction "VDD6_N1") (pintype "power_in"))
      (node (ref "U5") (pin "N9") (pinfunction "VDD7_N9") (pintype "power_in"))
      (node (ref "U5") (pin "R1") (pinfunction "VDD8_R1") (pintype "power_in"))
      (node (ref "U5") (pin "R9") (pinfunction "VDD9_R9") (pintype "power_in"))
    )
    (net (code "2") (name "+DDR_VREF") (class "Default")
      (node (ref "C10") (pin "1") (pinfunction "1_1") (pintype "passive"))
      (node (ref "C11") (pin "1") (pinfunction "1_1") (pintype "passive"))
      (node (ref "C18") (pin "2") (pinfunction "2_2") (pintype "passive"))
      (node (ref "C20") (pin "1") (pinfunction "1_1") (pintype "passive"))
      (node (ref "C3") (pin "1") (pinfunction "1_1") (pintype "passive"))
      (node (ref "C4") (pin "1") (pinfunction "1_1") (pintype "passive"))
      (node (ref "C5") (pin "1") (pinfunction "1_1") (pintype "passive"))
      (node (ref "C6") (pin "1") (pinfunction "1_1") (pintype "passive"))
      (node (ref "C7") (pin "1") (pinfunction "1_1") (pintype "passive"))
      (node (ref "C8") (pin "1") (pinfunction "1_1") (pintype "passive"))
      (node (ref "C9") (pin "1") (pinfunction "1_1") (pintype "passive"))
      (node (ref "R11") (pin "1") (pinfunction "1_1") (pintype "passive"))
      (node (ref "R12") (pin "2") (pinfunction "2_2") (pintype "passive"))
      (node (ref "U1") (pin "AC2") (pinfunction "DRAM_VREF_AC2") (pintype "power_in"))
      (node (ref "U2") (pin "H1") (pinfunction "VREFDQ_H1") (pintype "input"))
      (node (ref "U2") (pin "M8") (pinfunction "VREFCA_M8") (pintype "input"))
      (node (ref "U3") (pin "H1") (pinfunction "VREFDQ_H1") (pintype "input"))
      (node (ref "U3") (pin "M8") (pinfunction "VREFCA_M8") (pintype "input"))
      (node (ref "U4") (pin "H1") (pinfunction "VREFDQ_H1") (pintype "input"))
      (node (ref "U4") (pin "M8") (pinfunction "VREFCA_M8") (pintype "input"))
      (node (ref "U5") (pin "H1") (pinfunction "VREFDQ_H1") (pintype "input"))
      (node (ref "U5") (pin "M8") (pinfunction "VREFCA_M8") (pintype "input"))
    )
    (net (code "3") (name "/DRAM0_ZQ") (class "Default")
      (node (ref "R4") (pin "2") (pinfunction "2_2") (pintype "passive"))
      (node (ref "U2") (pin "L8") (pinfunction "ZQ_L8") (pintype "passive"))
    )
    (net (code "4") (name "/DRAM1_ZQ") (class "Default")
      (node (ref "R5") (pin "2") (pinfunction "2_2") (pintype "passive"))
      (node (ref "U3") (pin "L8") (pinfunction "ZQ_L8") (pintype "passive"))
    )
    (net (code "5") (name "/DRAM2_ZQ") (class "Default")
      (node (ref "R8") (pin "2") (pinfunction "2_2") (pintype "passive"))
      (node (ref "U4") (pin "L8") (pinfunction "ZQ_L8") (pintype "passive"))
    )
    (net (code "6") (name "/DRAM3_ZQ") (class "Default")
      (node (ref "R9") (pin "2") (pinfunction "2_2") (pintype "passive"))
      (node (ref "U5") (pin "L8") (pinfunction "ZQ_L8") (pintype "passive"))
    )
    (net (code "7") (name "/DRAM_A0") (class "Default")
      (node (ref "U1") (pin "AC14") (pinfunction "DRAM_A0_AC14") (pintype "output"))
      (node (ref "U2") (pin "N3") (pinfunction "A0_N3") (pintype "input"))
      (node (ref "U3") (pin "N3") (pinfunction "A0_N3") (pintype "input"))
      (node (ref "U4") (pin "N3") (pinfunction "A0_N3") (pintype "input"))
      (node (ref "U5") (pin "N3") (pinfunction "A0_N3") (pintype "input"))
    )
    (net (code "8") (name "/DRAM_A1") (class "Default")
      (node (ref "U1") (pin "AB14") (pinfunction "DRAM_A1_AB14") (pintype "output"))
      (node (ref "U2") (pin "P7") (pinfunction "A1_P7") (pintype "input"))
      (node (ref "U3") (pin "P7") (pinfunction "A1_P7") (pintype "input"))
      (node (ref "U4") (pin "P7") (pinfunction "A1_P7") (pintype "input"))
      (node (ref "U5") (pin "P7") (pinfunction "A1_P7") (pintype "input"))
    )
    (net (code "9") (name "/DRAM_A2") (class "Default")
      (node (ref "U1") (pin "AA14") (pinfunction "DRAM_A2_AA14") (pintype "output"))
      (node (ref "U2") (pin "P3") (pinfunction "A2_P3") (pintype "input"))
      (node (ref "U3") (pin "P3") (pinfunction "A2_P3") (pintype "input"))
      (node (ref "U4") (pin "P3") (pinfunction "A2_P3") (pintype "input"))
      (node (ref "U5") (pin "P3") (pinfunction "A2_P3") (pintype "input"))
    )
    (net (code "10") (name "/DRAM_A3") (class "Default")
      (node (ref "U1") (pin "Y14") (pinfunction "DRAM_A3_Y14") (pintype "output"))
      (node (ref "U2") (pin "N2") (pinfunction "A3_N2") (pintype "input"))
      (node (ref "U3") (pin "N2") (pinfunction "A3_N2") (pintype "input"))
      (node (ref "U4") (pin "N2") (pinfunction "A3_N2") (pintype "input"))
      (node (ref "U5") (pin "N2") (pinfunction "A3_N2") (pintype "input"))
    )
    (net (code "11") (name "/DRAM_A4") (class "Default")
      (node (ref "U1") (pin "W14") (pinfunction "DRAM_A4_W14") (pintype "output"))
      (node (ref "U2") (pin "P8") (pinfunction "A4_P8") (pintype "input"))
      (node (ref "U3") (pin "P8") (pinfunction "A4_P8") (pintype "input"))
      (node (ref "U4") (pin "P8") (pinfunction "A4_P8") (pintype "input"))
      (node (ref "U5") (pin "P8") (pinfunction "A4_P8") (pintype "input"))
    )
    (net (code "12") (name "/DRAM_A5") (class "Default")
      (node (ref "U1") (pin "AE13") (pinfunction "DRAM_A5_AE13") (pintype "output"))
      (node (ref "U2") (pin "P2") (pinfunction "A5_P2") (pintype "input"))
      (node (ref "U3") (pin "P2") (pinfunction "A5_P2") (pintype "input"))
      (node (ref "U4") (pin "P2") (pinfunction "A5_P2") (pintype "input"))
      (node (ref "U5") (pin "P2") (pinfunction "A5_P2") (pintype "input"))
    )
    (net (code "13") (name "/DRAM_A6") (class "Default")
      (node (ref "U1") (pin "AC13") (pinfunction "DRAM_A6_AC13") (pintype "output"))
      (node (ref "U2") (pin "R8") (pinfunction "A6_R8") (pintype "input"))
      (node (ref "U3") (pin "R8") (pinfunction "A6_R8") (pintype "input"))
      (node (ref "U4") (pin "R8") (pinfunction "A6_R8") (pintype "input"))
      (node (ref "U5") (pin "R8") (pinfunction "A6_R8") (pintype "input"))
    )
    (net (code "14") (name "/DRAM_A7") (class "Default")
      (node (ref "U1") (pin "Y13") (pinfunction "DRAM_A7_Y13") (pintype "output"))
      (node (ref "U2") (pin "R2") (pinfunction "A7_R2") (pintype "input"))
      (node (ref "U3") (pin "R2") (pinfunction "A7_R2") (pintype "input"))
      (node (ref "U4") (pin "R2") (pinfunction "A7_R2") (pintype "input"))
      (node (ref "U5") (pin "R2") (pinfunction "A7_R2") (pintype "input"))
    )
    (net (code "15") (name "/DRAM_A8") (class "Default")
      (node (ref "U1") (pin "AB13") (pinfunction "DRAM_A8_AB13") (pintype "output"))
      (node (ref "U2") (pin "T8") (pinfunction "A8_T8") (pintype "input"))
      (node (ref "U3") (pin "T8") (pinfunction "A8_T8") (pintype "input"))
      (node (ref "U4") (pin "T8") (pinfunction "A8_T8") (pintype "input"))
      (node (ref "U5") (pin "T8") (pinfunction "A8_T8") (pintype "input"))
    )
    (net (code "16") (name "/DRAM_A9") (class "Default")
      (node (ref "U1") (pin "AE12") (pinfunction "DRAM_A9_AE12") (pintype "output"))
      (node (ref "U2") (pin "R3") (pinfunction "A9_R3") (pintype "input"))
      (node (ref "U3") (pin "R3") (pinfunction "A9_R3") (pintype "input"))
      (node (ref "U4") (pin "R3") (pinfunction "A9_R3") (pintype "input"))
      (node (ref "U5") (pin "R3") (pinfunction "A9_R3") (pintype "input"))
    )
    (net (code "17") (name "/DRAM_A10") (class "Default")
      (node (ref "U1") (pin "AA15") (pinfunction "DRAM_A10_AA15") (pintype "output"))
      (node (ref "U2") (pin "L7") (pinfunction "A10/AP_L7") (pintype "input"))
      (node (ref "U3") (pin "L7") (pinfunction "A10/AP_L7") (pintype "input"))
      (node (ref "U4") (pin "L7") (pinfunction "A10/AP_L7") (pintype "input"))
      (node (ref "U5") (pin "L7") (pinfunction "A10/AP_L7") (pintype "input"))
    )
    (net (code "18") (name "/DRAM_A11") (class "Default")
      (node (ref "U1") (pin "AC12") (pinfunction "DRAM_A11_AC12") (pintype "output"))
      (node (ref "U2") (pin "R7") (pinfunction "A11_R7") (pintype "input"))
      (node (ref "U3") (pin "R7") (pinfunction "A11_R7") (pintype "input"))
      (node (ref "U4") (pin "R7") (pinfunction "A11_R7") (pintype "input"))
      (node (ref "U5") (pin "R7") (pinfunction "A11_R7") (pintype "input"))
    )
    (net (code "19") (name "/DRAM_A12") (class "Default")
      (node (ref "U1") (pin "AD12") (pinfunction "DRAM_A12_AD12") (pintype "output"))
      (node (ref "U2") (pin "N7") (pinfunction "A12/~{BC}_N7") (pintype "input"))
      (node (ref "U3") (pin "N7") (pinfunction "A12/~{BC}_N7") (pintype "input"))
      (node (ref "U4") (pin "N7") (pinfunction "A12/~{BC}_N7") (pintype "input"))
      (node (ref "U5") (pin "N7") (pinfunction "A12/~{BC}_N7") (pintype "input"))
    )
    (net (code "20") (name "/DRAM_A13") (class "Default")
      (node (ref "U1") (pin "AC17") (pinfunction "DRAM_A13_AC17") (pintype "output"))
      (node (ref "U2") (pin "T3") (pinfunction "A13_T3") (pintype "input"))
      (node (ref "U3") (pin "T3") (pinfunction "A13_T3") (pintype "input"))
      (node (ref "U4") (pin "T3") (pinfunction "A13_T3") (pintype "input"))
      (node (ref "U5") (pin "T3") (pinfunction "A13_T3") (pintype "input"))
    )
    (net (code "21") (name "/DRAM_A14") (class "Default")
      (node (ref "U1") (pin "AA12") (pinfunction "DRAM_A14_AA12") (pintype "output"))
      (node (ref "U2") (pin "T7") (pinfunction "NC_T7_T7") (pintype "passive"))
      (node (ref "U3") (pin "T7") (pinfunction "NC_T7_T7") (pintype "passive"))
      (node (ref "U4") (pin "T7") (pinfunction "NC_T7_T7") (pintype "passive"))
      (node (ref "U5") (pin "T7") (pinfunction "NC_T7_T7") (pintype "passive"))
    )
    (net (code "22") (name "/DRAM_A15") (class "Default")
      (node (ref "U1") (pin "Y12") (pinfunction "DRAM_A15_Y12") (pintype "output"))
      (node (ref "U2") (pin "M7") (pinfunction "NC_M7_M7") (pintype "passive"))
      (node (ref "U3") (pin "M7") (pinfunction "NC_M7_M7") (pintype "passive"))
      (node (ref "U4") (pin "M7") (pinfunction "NC_M7_M7") (pintype "passive"))
      (node (ref "U5") (pin "M7") (pinfunction "NC_M7_M7") (pintype "passive"))
    )
    (net (code "24") (name "/DRAM_CAS_B") (class "Default")
      (node (ref "U1") (pin "AE16") (pinfunction "DRAM_CAS_AE16") (pintype "output"))
      (node (ref "U2") (pin "K3") (pinfunction "~{CAS}_K3") (pintype "input"))
      (node (ref "U3") (pin "K3") (pinfunction "~{CAS}_K3") (pintype "input"))
      (node (ref "U4") (pin "K3") (pinfunction "~{CAS}_K3") (pintype "input"))
      (node (ref "U5") (pin "K3") (pinfunction "~{CAS}_K3") (pintype "input"))
    )
    (net (code "25") (name "/DRAM_CLK0_N") (class "Default")
      (node (ref "R2") (pin "1") (pinfunction "1_1") (pintype "passive"))
      (node (ref "U1") (pin "AE15") (pinfunction "~{DRAM_SDCLK_0}_AE15") (pintype "output"))
      (node (ref "U4") (pin "K7") (pinfunction "~{CK}_K7") (pintype "input"))
      (node (ref "U5") (pin "K7") (pinfunction "~{CK}_K7") (pintype "input"))
    )
    (net (code "26") (name "/DRAM_CLK0_P") (class "Default")
      (node (ref "R2") (pin "2") (pinfunction "2_2") (pintype "passive"))
      (node (ref "U1") (pin "AD15") (pinfunction "DRAM_SDCLK_0_AD15") (pintype "output"))
      (node (ref "U4") (pin "J7") (pinfunction "CK_J7") (pintype "input"))
      (node (ref "U5") (pin "J7") (pinfunction "CK_J7") (pintype "input"))
    )
    (net (code "27") (name "/DRAM_CLK1_N") (class "Default")
      (node (ref "R3") (pin "1") (pinfunction "1_1") (pintype "passive"))
      (node (ref "U1") (pin "AE14") (pinfunction "~{DRAM_SDCLK_1}_AE14") (pintype "output"))
      (node (ref "U2") (pin "K7") (pinfunction "~{CK}_K7") (pintype "input"))
      (node (ref "U3") (pin "K7") (pinfunction "~{CK}_K7") (pintype "input"))
    )
    (net (code "28") (name "/DRAM_CLK1_P") (class "Default")
      (node (ref "R3") (pin "2") (pinfunction "2_2") (pintype "passive"))
      (node (ref "U1") (pin "AD14") (pinfunction "DRAM_SDCLK_1_AD14") (pintype "output"))
      (node (ref "U2") (pin "J7") (pinfunction "CK_J7") (pintype "input"))
      (node (ref "U3") (pin "J7") (pinfunction "CK_J7") (pintype "input"))
    )
    (net (code "29") (name "/DRAM_CS0_B") (class "Default")
      (node (ref "U1") (pin "Y16") (pinfunction "DRAM_CS0_Y16") (pintype "output"))
      (node (ref "U2") (pin "L2") (pinfunction "~{CS}_L2") (pintype "input"))
      (node (ref "U3") (pin "L2") (pinfunction "~{CS}_L2") (pintype "input"))
      (node (ref "U4") (pin "L2") (pinfunction "~{CS}_L2") (pintype "input"))
      (node (ref "U5") (pin "L2") (pinfunction "~{CS}_L2") (pintype "input"))
    )
    (net (code "30") (name "/DRAM_D0") (class "Default")
      (node (ref "U1") (pin "AD2") (pinfunction "DRAM_D0_AD2") (pintype "bidirectional"))
      (node (ref "U2") (pin "D7") (pinfunction "DQ8_D7") (pintype "bidirectional"))
    )
    (net (code "31") (name "/DRAM_D1") (class "Default")
      (node (ref "U1") (pin "AE2") (pinfunction "DRAM_D1_AE2") (pintype "bidirectional"))
      (node (ref "U2") (pin "B8") (pinfunction "DQ14_B8") (pintype "bidirectional"))
    )
    (net (code "32") (name "/DRAM_D2") (class "Default")
      (node (ref "U1") (pin "AC4") (pinfunction "DRAM_D2_AC4") (pintype "bidirectional"))
      (node (ref "U2") (pin "C8") (pinfunction "DQ10_C8") (pintype "bidirectional"))
    )
    (net (code "33") (name "/DRAM_D3") (class "Default")
      (node (ref "U1") (pin "AA5") (pinfunction "DRAM_D3_AA5") (pintype "bidirectional"))
      (node (ref "U2") (pin "A3") (pinfunction "DQ15_A3") (pintype "bidirectional"))
    )
    (net (code "34") (name "/DRAM_D4") (class "Default")
      (node (ref "U1") (pin "AC1") (pinfunction "DRAM_D4_AC1") (pintype "bidirectional"))
      (node (ref "U2") (pin "C2") (pinfunction "DQ11_C2") (pintype "bidirectional"))
    )
    (net (code "35") (name "/DRAM_D5") (class "Default")
      (node (ref "U1") (pin "AD1") (pinfunction "DRAM_D5_AD1") (pintype "bidirectional"))
      (node (ref "U2") (pin "C3") (pinfunction "DQ9_C3") (pintype "bidirectional"))
    )
    (net (code "36") (name "/DRAM_D6") (class "Default")
      (node (ref "U1") (pin "AB4") (pinfunction "DRAM_D6_AB4") (pintype "bidirectional"))
      (node (ref "U2") (pin "A2") (pinfunction "DQ13_A2") (pintype "bidirectional"))
    )
    (net (code "37") (name "/DRAM_D7") (class "Default")
      (node (ref "U1") (pin "AE4") (pinfunction "DRAM_D7_AE4") (pintype "bidirectional"))
      (node (ref "U2") (pin "A7") (pinfunction "DQ12_A7") (pintype "bidirectional"))
    )
    (net (code "38") (name "/DRAM_D8") (class "Default")
      (node (ref "U1") (pin "AD5") (pinfunction "DRAM_D8_AD5") (pintype "bidirectional"))
      (node (ref "U2") (pin "E3") (pinfunction "DQ0_E3") (pintype "bidirectional"))
    )
    (net (code "39") (name "/DRAM_D9") (class "Default")
      (node (ref "U1") (pin "AE5") (pinfunction "DRAM_D9_AE5") (pintype "bidirectional"))
      (node (ref "U2") (pin "F7") (pinfunction "DQ1_F7") (pintype "bidirectional"))
    )
    (net (code "40") (name "/DRAM_D10") (class "Default")
      (node (ref "U1") (pin "AA6") (pinfunction "DRAM_D10_AA6") (pintype "bidirectional"))
      (node (ref "U2") (pin "G2") (pinfunction "DQ6_G2") (pintype "bidirectional"))
    )
    (net (code "41") (name "/DRAM_D11") (class "Default")
      (node (ref "U1") (pin "AE7") (pinfunction "DRAM_D11_AE7") (pintype "bidirectional"))
      (node (ref "U2") (pin "H7") (pinfunction "DQ7_H7") (pintype "bidirectional"))
    )
    (net (code "42") (name "/DRAM_D12") (class "Default")
      (node (ref "U1") (pin "AB5") (pinfunction "DRAM_D12_AB5") (pintype "bidirectional"))
      (node (ref "U2") (pin "H3") (pinfunction "DQ4_H3") (pintype "bidirectional"))
    )
    (net (code "43") (name "/DRAM_D13") (class "Default")
      (node (ref "U1") (pin "AC5") (pinfunction "DRAM_D13_AC5") (pintype "bidirectional"))
      (node (ref "U2") (pin "F2") (pinfunction "DQ2_F2") (pintype "bidirectional"))
    )
    (net (code "44") (name "/DRAM_D14") (class "Default")
      (node (ref "U1") (pin "AB6") (pinfunction "DRAM_D14_AB6") (pintype "bidirectional"))
      (node (ref "U2") (pin "F8") (pinfunction "DQ3_F8") (pintype "bidirectional"))
    )
    (net (code "45") (name "/DRAM_D15") (class "Default")
      (node (ref "U1") (pin "AC7") (pinfunction "DRAM_D15_AC7") (pintype "bidirectional"))
      (node (ref "U2") (pin "H8") (pinfunction "DQ5_H8") (pintype "bidirectional"))
    )
    (net (code "46") (name "/DRAM_D16") (class "Default")
      (node (ref "U1") (pin "AB7") (pinfunction "DRAM_D16_AB7") (pintype "bidirectional"))
      (node (ref "U3") (pin "E3") (pinfunction "DQ0_E3") (pintype "bidirectional"))
    )
    (net (code "47") (name "/DRAM_D17") (class "Default")
      (node (ref "U1") (pin "AA8") (pinfunction "DRAM_D17_AA8") (pintype "bidirectional"))
      (node (ref "U3") (pin "F8") (pinfunction "DQ3_F8") (pintype "bidirectional"))
    )
    (net (code "48") (name "/DRAM_D18") (class "Default")
      (node (ref "U1") (pin "AB9") (pinfunction "DRAM_D18_AB9") (pintype "bidirectional"))
      (node (ref "U3") (pin "H7") (pinfunction "DQ7_H7") (pintype "bidirectional"))
    )
    (net (code "49") (name "/DRAM_D19") (class "Default")
      (node (ref "U1") (pin "Y9") (pinfunction "DRAM_D19_Y9") (pintype "bidirectional"))
      (node (ref "U3") (pin "H3") (pinfunction "DQ4_H3") (pintype "bidirectional"))
    )
    (net (code "50") (name "/DRAM_D20") (class "Default")
      (node (ref "U1") (pin "Y7") (pinfunction "DRAM_D20_Y7") (pintype "bidirectional"))
      (node (ref "U3") (pin "H8") (pinfunction "DQ5_H8") (pintype "bidirectional"))
    )
    (net (code "51") (name "/DRAM_D21") (class "Default")
      (node (ref "U1") (pin "Y8") (pinfunction "DRAM_D21_Y8") (pintype "bidirectional"))
      (node (ref "U3") (pin "G2") (pinfunction "DQ6_G2") (pintype "bidirectional"))
    )
    (net (code "52") (name "/DRAM_D22") (class "Default")
      (node (ref "U1") (pin "AC8") (pinfunction "DRAM_D22_AC8") (pintype "bidirectional"))
      (node (ref "U3") (pin "F7") (pinfunction "DQ1_F7") (pintype "bidirectional"))
    )
    (net (code "53") (name "/DRAM_D23") (class "Default")
      (node (ref "U1") (pin "AA9") (pinfunction "DRAM_D23_AA9") (pintype "bidirectional"))
      (node (ref "U3") (pin "F2") (pinfunction "DQ2_F2") (pintype "bidirectional"))
    )
    (net (code "54") (name "/DRAM_D24") (class "Default")
      (node (ref "U1") (pin "AE9") (pinfunction "DRAM_D24_AE9") (pintype "bidirectional"))
      (node (ref "U3") (pin "D7") (pinfunction "DQ8_D7") (pintype "bidirectional"))
    )
    (net (code "55") (name "/DRAM_D25") (class "Default")
      (node (ref "U1") (pin "Y10") (pinfunction "DRAM_D25_Y10") (pintype "bidirectional"))
      (node (ref "U3") (pin "A7") (pinfunction "DQ12_A7") (pintype "bidirectional"))
    )
    (net (code "56") (name "/DRAM_D26") (class "Default")
      (node (ref "U1") (pin "AE11") (pinfunction "DRAM_D26_AE11") (pintype "bidirectional"))
      (node (ref "U3") (pin "C3") (pinfunction "DQ9_C3") (pintype "bidirectional"))
    )
    (net (code "57") (name "/DRAM_D27") (class "Default")
      (node (ref "U1") (pin "AB11") (pinfunction "DRAM_D27_AB11") (pintype "bidirectional"))
      (node (ref "U3") (pin "C2") (pinfunction "DQ11_C2") (pintype "bidirectional"))
    )
    (net (code "58") (name "/DRAM_D28") (class "Default")
      (node (ref "U1") (pin "AC9") (pinfunction "DRAM_D28_AC9") (pintype "bidirectional"))
      (node (ref "U3") (pin "C8") (pinfunction "DQ10_C8") (pintype "bidirectional"))
    )
    (net (code "59") (name "/DRAM_D29") (class "Default")
      (node (ref "U1") (pin "AD9") (pinfunction "DRAM_D29_AD9") (pintype "bidirectional"))
      (node (ref "U3") (pin "B8") (pinfunction "DQ14_B8") (pintype "bidirectional"))
    )
    (net (code "60") (name "/DRAM_D30") (class "Default")
      (node (ref "U1") (pin "AD11") (pinfunction "DRAM_D30_AD11") (pintype "bidirectional"))
      (node (ref "U3") (pin "A2") (pinfunction "DQ13_A2") (pintype "bidirectional"))
    )
    (net (code "61") (name "/DRAM_D31") (class "Default")
      (node (ref "U1") (pin "AC11") (pinfunction "DRAM_D31_AC11") (pintype "bidirectional"))
      (node (ref "U3") (pin "A3") (pinfunction "DQ15_A3") (pintype "bidirectional"))
    )
    (net (code "62") (name "/DRAM_D32") (class "Default")
      (node (ref "U1") (pin "AA17") (pinfunction "DRAM_D32_AA17") (pintype "bidirectional"))
      (node (ref "U5") (pin "E3") (pinfunction "DQ0_E3") (pintype "bidirectional"))
    )
    (net (code "63") (name "/DRAM_D33") (class "Default")
      (node (ref "U1") (pin "AA18") (pinfunction "DRAM_D33_AA18") (pintype "bidirectional"))
      (node (ref "U5") (pin "G2") (pinfunction "DQ6_G2") (pintype "bidirectional"))
    )
    (net (code "64") (name "/DRAM_D34") (class "Default")
      (node (ref "U1") (pin "AC18") (pinfunction "DRAM_D34_AC18") (pintype "bidirectional"))
      (node (ref "U5") (pin "F8") (pinfunction "DQ3_F8") (pintype "bidirectional"))
    )
    (net (code "65") (name "/DRAM_D35") (class "Default")
      (node (ref "U1") (pin "AE19") (pinfunction "DRAM_D35_AE19") (pintype "bidirectional"))
      (node (ref "U5") (pin "H7") (pinfunction "DQ7_H7") (pintype "bidirectional"))
    )
    (net (code "66") (name "/DRAM_D36") (class "Default")
      (node (ref "U1") (pin "Y17") (pinfunction "DRAM_D36_Y17") (pintype "bidirectional"))
      (node (ref "U5") (pin "H3") (pinfunction "DQ4_H3") (pintype "bidirectional"))
    )
    (net (code "67") (name "/DRAM_D37") (class "Default")
      (node (ref "U1") (pin "Y18") (pinfunction "DRAM_D37_Y18") (pintype "bidirectional"))
      (node (ref "U5") (pin "F2") (pinfunction "DQ2_F2") (pintype "bidirectional"))
    )
    (net (code "68") (name "/DRAM_D38") (class "Default")
      (node (ref "U1") (pin "AB19") (pinfunction "DRAM_D38_AB19") (pintype "bidirectional"))
      (node (ref "U5") (pin "H8") (pinfunction "DQ5_H8") (pintype "bidirectional"))
    )
    (net (code "69") (name "/DRAM_D39") (class "Default")
      (node (ref "U1") (pin "AC19") (pinfunction "DRAM_D39_AC19") (pintype "bidirectional"))
      (node (ref "U5") (pin "F7") (pinfunction "DQ1_F7") (pintype "bidirectional"))
    )
    (net (code "70") (name "/DRAM_D40") (class "Default")
      (node (ref "U1") (pin "Y19") (pinfunction "DRAM_D40_Y19") (pintype "bidirectional"))
      (node (ref "U5") (pin "D7") (pinfunction "DQ8_D7") (pintype "bidirectional"))
    )
    (net (code "71") (name "/DRAM_D41") (class "Default")
      (node (ref "U1") (pin "AB20") (pinfunction "DRAM_D41_AB20") (pintype "bidirectional"))
      (node (ref "U5") (pin "B8") (pinfunction "DQ14_B8") (pintype "bidirectional"))
    )
    (net (code "72") (name "/DRAM_D42") (class "Default")
      (node (ref "U1") (pin "AB21") (pinfunction "DRAM_D42_AB21") (pintype "bidirectional"))
      (node (ref "U5") (pin "C2") (pinfunction "DQ11_C2") (pintype "bidirectional"))
    )
    (net (code "73") (name "/DRAM_D43") (class "Default")
      (node (ref "U1") (pin "AD21") (pinfunction "DRAM_D43_AD21") (pintype "bidirectional"))
      (node (ref "U5") (pin "A7") (pinfunction "DQ12_A7") (pintype "bidirectional"))
    )
    (net (code "74") (name "/DRAM_D44") (class "Default")
      (node (ref "U1") (pin "Y20") (pinfunction "DRAM_D44_Y20") (pintype "bidirectional"))
      (node (ref "U5") (pin "A2") (pinfunction "DQ13_A2") (pintype "bidirectional"))
    )
    (net (code "75") (name "/DRAM_D45") (class "Default")
      (node (ref "U1") (pin "AA20") (pinfunction "DRAM_D45_AA20") (pintype "bidirectional"))
      (node (ref "U5") (pin "C8") (pinfunction "DQ10_C8") (pintype "bidirectional"))
    )
    (net (code "76") (name "/DRAM_D46") (class "Default")
      (node (ref "U1") (pin "AE21") (pinfunction "DRAM_D46_AE21") (pintype "bidirectional"))
      (node (ref "U5") (pin "A3") (pinfunction "DQ15_A3") (pintype "bidirectional"))
    )
    (net (code "77") (name "/DRAM_D47") (class "Default")
      (node (ref "U1") (pin "AC21") (pinfunction "DRAM_D47_AC21") (pintype "bidirectional"))
      (node (ref "U5") (pin "C3") (pinfunction "DQ9_C3") (pintype "bidirectional"))
    )
    (net (code "78") (name "/DRAM_D48") (class "Default")
      (node (ref "U1") (pin "AC22") (pinfunction "DRAM_D48_AC22") (pintype "bidirectional"))
      (node (ref "U4") (pin "D7") (pinfunction "DQ8_D7") (pintype "bidirectional"))
    )
    (net (code "79") (name "/DRAM_D49") (class "Default")
      (node (ref "U1") (pin "AE22") (pinfunction "DRAM_D49_AE22") (pintype "bidirectional"))
      (node (ref "U4") (pin "C2") (pinfunction "DQ11_C2") (pintype "bidirectional"))
    )
    (net (code "80") (name "/DRAM_D50") (class "Default")
      (node (ref "U1") (pin "AE24") (pinfunction "DRAM_D50_AE24") (pintype "bidirectional"))
      (node (ref "U4") (pin "C3") (pinfunction "DQ9_C3") (pintype "bidirectional"))
    )
    (net (code "81") (name "/DRAM_D51") (class "Default")
      (node (ref "U1") (pin "AC24") (pinfunction "DRAM_D51_AC24") (pintype "bidirectional"))
      (node (ref "U4") (pin "B8") (pinfunction "DQ14_B8") (pintype "bidirectional"))
    )
    (net (code "82") (name "/DRAM_D52") (class "Default")
      (node (ref "U1") (pin "AB22") (pinfunction "DRAM_D52_AB22") (pintype "bidirectional"))
      (node (ref "U4") (pin "A7") (pinfunction "DQ12_A7") (pintype "bidirectional"))
    )
    (net (code "83") (name "/DRAM_D53") (class "Default")
      (node (ref "U1") (pin "AC23") (pinfunction "DRAM_D53_AC23") (pintype "bidirectional"))
      (node (ref "U4") (pin "C8") (pinfunction "DQ10_C8") (pintype "bidirectional"))
    )
    (net (code "84") (name "/DRAM_D54") (class "Default")
      (node (ref "U1") (pin "AD25") (pinfunction "DRAM_D54_AD25") (pintype "bidirectional"))
      (node (ref "U4") (pin "A3") (pinfunction "DQ15_A3") (pintype "bidirectional"))
    )
    (net (code "85") (name "/DRAM_D55") (class "Default")
      (node (ref "U1") (pin "AC25") (pinfunction "DRAM_D55_AC25") (pintype "bidirectional"))
      (node (ref "U4") (pin "A2") (pinfunction "DQ13_A2") (pintype "bidirectional"))
    )
    (net (code "86") (name "/DRAM_D56") (class "Default")
      (node (ref "U1") (pin "AB25") (pinfunction "DRAM_D56_AB25") (pintype "bidirectional"))
      (node (ref "U4") (pin "E3") (pinfunction "DQ0_E3") (pintype "bidirectional"))
    )
    (net (code "87") (name "/DRAM_D57") (class "Default")
      (node (ref "U1") (pin "AA21") (pinfunction "DRAM_D57_AA21") (pintype "bidirectional"))
      (node (ref "U4") (pin "G2") (pinfunction "DQ6_G2") (pintype "bidirectional"))
    )
    (net (code "88") (name "/DRAM_D58") (class "Default")
      (node (ref "U1") (pin "Y25") (pinfunction "DRAM_D58_Y25") (pintype "bidirectional"))
      (node (ref "U4") (pin "H7") (pinfunction "DQ7_H7") (pintype "bidirectional"))
    )
    (net (code "89") (name "/DRAM_D59") (class "Default")
      (node (ref "U1") (pin "Y22") (pinfunction "DRAM_D59_Y22") (pintype "bidirectional"))
      (node (ref "U4") (pin "F7") (pinfunction "DQ1_F7") (pintype "bidirectional"))
    )
    (net (code "90") (name "/DRAM_D60") (class "Default")
      (node (ref "U1") (pin "AB23") (pinfunction "DRAM_D60_AB23") (pintype "bidirectional"))
      (node (ref "U4") (pin "H3") (pinfunction "DQ4_H3") (pintype "bidirectional"))
    )
    (net (code "91") (name "/DRAM_D61") (class "Default")
      (node (ref "U1") (pin "AA23") (pinfunction "DRAM_D61_AA23") (pintype "bidirectional"))
      (node (ref "U4") (pin "F2") (pinfunction "DQ2_F2") (pintype "bidirectional"))
    )
    (net (code "92") (name "/DRAM_D62") (class "Default")
      (node (ref "U1") (pin "Y23") (pinfunction "DRAM_D62_Y23") (pintype "bidirectional"))
      (node (ref "U4") (pin "F8") (pinfunction "DQ3_F8") (pintype "bidirectional"))
    )
    (net (code "93") (name "/DRAM_D63") (class "Default")
      (node (ref "U1") (pin "W25") (pinfunction "DRAM_D63_W25") (pintype "bidirectional"))
      (node (ref "U4") (pin "H8") (pinfunction "DQ5_H8") (pintype "bidirectional"))
    )
    (net (code "94") (name "/DRAM_DQM0") (class "Default")
      (node (ref "U1") (pin "AC3") (pinfunction "DRAM_DQM0_AC3") (pintype "output"))
      (node (ref "U2") (pin "D3") (pinfunction "UDM_D3") (pintype "input"))
    )
    (net (code "95") (name "/DRAM_DQM1") (class "Default")
      (node (ref "U1") (pin "AC6") (pinfunction "DRAM_DQM1_AC6") (pintype "output"))
      (node (ref "U2") (pin "E7") (pinfunction "LDM_E7") (pintype "input"))
    )
    (net (code "96") (name "/DRAM_DQM2") (class "Default")
      (node (ref "U1") (pin "AB8") (pinfunction "DRAM_DQM2_AB8") (pintype "output"))
      (node (ref "U3") (pin "E7") (pinfunction "LDM_E7") (pintype "input"))
    )
    (net (code "97") (name "/DRAM_DQM3") (class "Default")
      (node (ref "U1") (pin "AE10") (pinfunction "DRAM_DQM3_AE10") (pintype "output"))
      (node (ref "U3") (pin "D3") (pinfunction "UDM_D3") (pintype "input"))
    )
    (net (code "98") (name "/DRAM_DQM4") (class "Default")
      (node (ref "U1") (pin "AB18") (pinfunction "DRAM_DQM4_AB18") (pintype "output"))
      (node (ref "U5") (pin "E7") (pinfunction "LDM_E7") (pintype "input"))
    )
    (net (code "99") (name "/DRAM_DQM5") (class "Default")
      (node (ref "U1") (pin "AC20") (pinfunction "DRAM_DQM5_AC20") (pintype "output"))
      (node (ref "U5") (pin "D3") (pinfunction "UDM_D3") (pintype "input"))
    )
    (net (code "100") (name "/DRAM_DQM6") (class "Default")
      (node (ref "U1") (pin "AD24") (pinfunction "DRAM_DQM6_AD24") (pintype "output"))
      (node (ref "U4") (pin "D3") (pinfunction "UDM_D3") (pintype "input"))
    )
    (net (code "101") (name "/DRAM_DQM7") (class "Default")
      (node (ref "U1") (pin "Y21") (pinfunction "DRAM_DQM7_Y21") (pintype "output"))
      (node (ref "U4") (pin "E7") (pinfunction "LDM_E7") (pintype "input"))
    )
    (net (code "102") (name "/DRAM_DQS0_N") (class "Default")
      (node (ref "U1") (pin "AD3") (pinfunction "~{DRAM_SDQS0}_AD3") (pintype "bidirectional"))
      (node (ref "U2") (pin "B7") (pinfunction "~{UDQS}_B7") (pintype "bidirectional"))
    )
    (net (code "103") (name "/DRAM_DQS0_P") (class "Default")
      (node (ref "U1") (pin "AE3") (pinfunction "DRAM_SDQS0_AE3") (pintype "bidirectional"))
      (node (ref "U2") (pin "C7") (pinfunction "UDQS_C7") (pintype "bidirectional"))
    )
    (net (code "104") (name "/DRAM_DQS1_N") (class "Default")
      (node (ref "U1") (pin "AE6") (pinfunction "~{DRAM_SDQS1}_AE6") (pintype "bidirectional"))
      (node (ref "U2") (pin "G3") (pinfunction "~{LDQS}_G3") (pintype "bidirectional"))
    )
    (net (code "105") (name "/DRAM_DQS1_P") (class "Default")
      (node (ref "U1") (pin "AD6") (pinfunction "DRAM_SDQS1_AD6") (pintype "bidirectional"))
      (node (ref "U2") (pin "F3") (pinfunction "LDQS_F3") (pintype "bidirectional"))
    )
    (net (code "106") (name "/DRAM_DQS2_N") (class "Default")
      (node (ref "U1") (pin "AE8") (pinfunction "~{DRAM_SDQS2}_AE8") (pintype "bidirectional"))
      (node (ref "U3") (pin "G3") (pinfunction "~{LDQS}_G3") (pintype "bidirectional"))
    )
    (net (code "107") (name "/DRAM_DQS2_P") (class "Default")
      (node (ref "U1") (pin "AD8") (pinfunction "DRAM_SDQS2_AD8") (pintype "bidirectional"))
      (node (ref "U3") (pin "F3") (pinfunction "LDQS_F3") (pintype "bidirectional"))
    )
    (net (code "108") (name "/DRAM_DQS3_N") (class "Default")
      (node (ref "U1") (pin "AB10") (pinfunction "~{DRAM_SDQS3}_AB10") (pintype "bidirectional"))
      (node (ref "U3") (pin "B7") (pinfunction "~{UDQS}_B7") (pintype "bidirectional"))
    )
    (net (code "109") (name "/DRAM_DQS3_P") (class "Default")
      (node (ref "U1") (pin "AC10") (pinfunction "DRAM_SDQS3_AC10") (pintype "bidirectional"))
      (node (ref "U3") (pin "C7") (pinfunction "UDQS_C7") (pintype "bidirectional"))
    )
    (net (code "110") (name "/DRAM_DQS4_N") (class "Default")
      (node (ref "U1") (pin "AE18") (pinfunction "~{DRAM_SDQS4}_AE18") (pintype "bidirectional"))
      (node (ref "U5") (pin "G3") (pinfunction "~{LDQS}_G3") (pintype "bidirectional"))
    )
    (net (code "111") (name "/DRAM_DQS4_P") (class "Default")
      (node (ref "U1") (pin "AD18") (pinfunction "DRAM_SDQS4_AD18") (pintype "bidirectional"))
      (node (ref "U5") (pin "F3") (pinfunction "LDQS_F3") (pintype "bidirectional"))
    )
    (net (code "112") (name "/DRAM_DQS5_N") (class "Default")
      (node (ref "U1") (pin "AE20") (pinfunction "~{DRAM_SDQS5}_AE20") (pintype "bidirectional"))
      (node (ref "U5") (pin "B7") (pinfunction "~{UDQS}_B7") (pintype "bidirectional"))
    )
    (net (code "113") (name "/DRAM_DQS5_P") (class "Default")
      (node (ref "U1") (pin "AD20") (pinfunction "DRAM_SDQS5_AD20") (pintype "bidirectional"))
      (node (ref "U5") (pin "C7") (pinfunction "UDQS_C7") (pintype "bidirectional"))
    )
    (net (code "114") (name "/DRAM_DQS6_N") (class "Default")
      (node (ref "U1") (pin "AE23") (pinfunction "~{DRAM_SDQS6}_AE23") (pintype "bidirectional"))
      (node (ref "U4") (pin "B7") (pinfunction "~{UDQS}_B7") (pintype "bidirectional"))
    )
    (net (code "115") (name "/DRAM_DQS6_P") (class "Default")
      (node (ref "U1") (pin "AD23") (pinfunction "DRAM_SDQS6_AD23") (pintype "bidirectional"))
      (node (ref "U4") (pin "C7") (pinfunction "UDQS_C7") (pintype "bidirectional"))
    )
    (net (code "116") (name "/DRAM_DQS7_N") (class "Default")
      (node (ref "U1") (pin "AA24") (pinfunction "~{DRAM_SDQS7}_AA24") (pintype "bidirectional"))
      (node (ref "U4") (pin "G3") (pinfunction "~{LDQS}_G3") (pintype "bidirectional"))
    )
    (net (code "117") (name "/DRAM_DQS7_P") (class "Default")
      (node (ref "U1") (pin "AA25") (pinfunction "DRAM_SDQS7_AA25") (pintype "bidirectional"))
      (node (ref "U4") (pin "F3") (pinfunction "LDQS_F3") (pintype "bidirectional"))
    )
    (net (code "119") (name "/DRAM_RAS_B") (class "Default")
      (node (ref "U1") (pin "AB15") (pinfunction "DRAM_RAS_AB15") (pintype "output"))
      (node (ref "U2") (pin "J3") (pinfunction "~{RAS}_J3") (pintype "input"))
      (node (ref "U3") (pin "J3") (pinfunction "~{RAS}_J3") (pintype "input"))
      (node (ref "U4") (pin "J3") (pinfunction "~{RAS}_J3") (pintype "input"))
      (node (ref "U5") (pin "J3") (pinfunction "~{RAS}_J3") (pintype "input"))
    )
    (net (code "120") (name "/DRAM_RESET_B") (class "Default")
      (node (ref "R7") (pin "2") (pinfunction "2_2") (pintype "passive"))
      (node (ref "U1") (pin "Y6") (pinfunction "DRAM_RESET_Y6") (pintype "output"))
      (node (ref "U2") (pin "T2") (pinfunction "~{RESET}_T2") (pintype "input"))
      (node (ref "U3") (pin "T2") (pinfunction "~{RESET}_T2") (pintype "input"))
      (node (ref "U4") (pin "T2") (pinfunction "~{RESET}_T2") (pintype "input"))
      (node (ref "U5") (pin "T2") (pinfunction "~{RESET}_T2") (pintype "input"))
    )
    (net (code "121") (name "/DRAM_SDBA0") (class "Default")
      (node (ref "U1") (pin "AC15") (pinfunction "DRAM_SDBA0_AC15") (pintype "output"))
      (node (ref "U2") (pin "M2") (pinfunction "BA0_M2") (pintype "input"))
      (node (ref "U3") (pin "M2") (pinfunction "BA0_M2") (pintype "input"))
      (node (ref "U4") (pin "M2") (pinfunction "BA0_M2") (pintype "input"))
      (node (ref "U5") (pin "M2") (pinfunction "BA0_M2") (pintype "input"))
    )
    (net (code "122") (name "/DRAM_SDBA1") (class "Default")
      (node (ref "U1") (pin "Y15") (pinfunction "DRAM_SDBA1_Y15") (pintype "output"))
      (node (ref "U2") (pin "N8") (pinfunction "BA1_N8") (pintype "input"))
      (node (ref "U3") (pin "N8") (pinfunction "BA1_N8") (pintype "input"))
      (node (ref "U4") (pin "N8") (pinfunction "BA1_N8") (pintype "input"))
      (node (ref "U5") (pin "N8") (pinfunction "BA1_N8") (pintype "input"))
    )
    (net (code "123") (name "/DRAM_SDBA2") (class "Default")
      (node (ref "U1") (pin "AB12") (pinfunction "DRAM_SDBA2_AB12") (pintype "output"))
      (node (ref "U2") (pin "M3") (pinfunction "BA2_M3") (pintype "input"))
      (node (ref "U3") (pin "M3") (pinfunction "BA2_M3") (pintype "input"))
      (node (ref "U4") (pin "M3") (pinfunction "BA2_M3") (pintype "input"))
      (node (ref "U5") (pin "M3") (pinfunction "BA2_M3") (pintype "input"))
    )
    (net (code "124") (name "/DRAM_SDCKE0") (class "Default")
      (node (ref "R6") (pin "2") (pinfunction "2_2") (pintype "passive"))
      (node (ref "U1") (pin "Y11") (pinfunction "DRAM_SDCKE0_Y11") (pintype "output"))
      (node (ref "U2") (pin "K9") (pinfunction "CKE_K9") (pintype "input"))
      (node (ref "U3") (pin "K9") (pinfunction "CKE_K9") (pintype "input"))
      (node (ref "U4") (pin "K9") (pinfunction "CKE_K9") (pintype "input"))
      (node (ref "U5") (pin "K9") (pinfunction "CKE_K9") (pintype "input"))
    )
    (net (code "125") (name "/DRAM_SDODT0") (class "Default")
      (node (ref "U1") (pin "AC16") (pinfunction "DRAM_SDODT0_AC16") (pintype "output"))
      (node (ref "U2") (pin "K1") (pinfunction "ODT_K1") (pintype "input"))
      (node (ref "U3") (pin "K1") (pinfunction "ODT_K1") (pintype "input"))
      (node (ref "U4") (pin "K1") (pinfunction "ODT_K1") (pintype "input"))
      (node (ref "U5") (pin "K1") (pinfunction "ODT_K1") (pintype "input"))
    )
    (net (code "126") (name "/DRAM_WE_B") (class "Default")
      (node (ref "U1") (pin "AB16") (pinfunction "DRAM_SDWE_AB16") (pintype "output"))
      (node (ref "U2") (pin "L3") (pinfunction "~{WE}_L3") (pintype "input"))
      (node (ref "U3") (pin "L3") (pinfunction "~{WE}_L3") (pintype "input"))
      (node (ref "U4") (pin "L3") (pinfunction "~{WE}_L3") (pintype "input"))
      (node (ref "U5") (pin "L3") (pinfunction "~{WE}_L3") (pintype "input"))
    )
    (net (code "127") (name "/ZQPAD") (class "Default")
      (node (ref "R10") (pin "1") (pinfunction "1_1") (pintype "passive"))
      (node (ref "U1") (pin "AE17") (pinfunction "ZQPAD_AE17") (pintype "passive"))
    )
    (net (code "128") (name "GND") (class "Default")
      (node (ref "C10") (pin "2") (pinfunction "2_2") (pintype "passive"))
      (node (ref "C11") (pin "2") (pinfunction "2_2") (pintype "passive"))
      (node (ref "C12") (pin "2") (pinfunction "2_2") (pintype "passive"))
      (node (ref "C13") (pin "2") (pinfunction "2_2") (pintype "passive"))
      (node (ref "C14") (pin "2") (pinfunction "2_2") (pintype "passive"))
      (node (ref "C15") (pin "2") (pinfunction "2_2") (pintype "passive"))
      (node (ref "C16") (pin "2") (pinfunction "2_2") (pintype "passive"))
      (node (ref "C17") (pin "2") (pinfunction "2_2") (pintype "passive"))
      (node (ref "C19") (pin "2") (pinfunction "2_2") (pintype "passive"))
      (node (ref "C20") (pin "2") (pinfunction "2_2") (pintype "passive"))
      (node (ref "C21") (pin "2") (pinfunction "2_2") (pintype "passive"))
      (node (ref "C22") (pin "2") (pinfunction "2_2") (pintype "passive"))
      (node (ref "C23") (pin "2") (pinfunction "2_2") (pintype "passive"))
      (node (ref "C24") (pin "2") (pinfunction "2_2") (pintype "passive"))
      (node (ref "C25") (pin "2") (pinfunction "2_2") (pintype "passive"))
      (node (ref "C26") (pin "2") (pinfunction "2_2") (pintype "passive"))
      (node (ref "C27") (pin "2") (pinfunction "2_2") (pintype "passive"))
      (node (ref "C28") (pin "2") (pinfunction "2_2") (pintype "passive"))
      (node (ref "C29") (pin "2") (pinfunction "2_2") (pintype "passive"))
      (node (ref "C3") (pin "2") (pinfunction "2_2") (pintype "passive"))
      (node (ref "C30") (pin "2") (pinfunction "2_2") (pintype "passive"))
      (node (ref "C31") (pin "2") (pinfunction "2_2") (pintype "passive"))
      (node (ref "C32") (pin "2") (pinfunction "2_2") (pintype "passive"))
      (node (ref "C33") (pin "2") (pinfunction "2_2") (pintype "passive"))
      (node (ref "C34") (pin "2") (pinfunction "2_2") (pintype "passive"))
      (node (ref "C35") (pin "2") (pinfunction "2_2") (pintype "passive"))
      (node (ref "C36") (pin "2") (pinfunction "2_2") (pintype "passive"))
      (node (ref "C37") (pin "2") (pinfunction "2_2") (pintype "passive"))
      (node (ref "C38") (pin "2") (pinfunction "2_2") (pintype "passive"))
      (node (ref "C39") (pin "2") (pinfunction "2_2") (pintype "passive"))
      (node (ref "C4") (pin "2") (pinfunction "2_2") (pintype "passive"))
      (node (ref "C40") (pin "2") (pinfunction "2_2") (pintype "passive"))
      (node (ref "C41") (pin "2") (pinfunction "2_2") (pintype "passive"))
      (node (ref "C42") (pin "2") (pinfunction "2_2") (pintype "passive"))
      (node (ref "C43") (pin "2") (pinfunction "2_2") (pintype "passive"))
      (node (ref "C44") (pin "2") (pinfunction "2_2") (pintype "passive"))
      (node (ref "C45") (pin "2") (pinfunction "2_2") (pintype "passive"))
      (node (ref "C46") (pin "2") (pinfunction "2_2") (pintype "passive"))
      (node (ref "C47") (pin "2") (pinfunction "2_2") (pintype "passive"))
      (node (ref "C48") (pin "2") (pinfunction "2_2") (pintype "passive"))
      (node (ref "C49") (pin "2") (pinfunction "2_2") (pintype "passive"))
      (node (ref "C5") (pin "2") (pinfunction "2_2") (pintype "passive"))
      (node (ref "C50") (pin "2") (pinfunction "2_2") (pintype "passive"))
      (node (ref "C51") (pin "2") (pinfunction "2_2") (pintype "passive"))
      (node (ref "C52") (pin "2") (pinfunction "2_2") (pintype "passive"))
      (node (ref "C53") (pin "2") (pinfunction "2_2") (pintype "passive"))
      (node (ref "C54") (pin "2") (pinfunction "2_2") (pintype "passive"))
      (node (ref "C55") (pin "2") (pinfunction "2_2") (pintype "passive"))
      (node (ref "C56") (pin "2") (pinfunction "2_2") (pintype "passive"))
      (node (ref "C57") (pin "2") (pinfunction "2_2") (pintype "passive"))
      (node (ref "C58") (pin "2") (pinfunction "2_2") (pintype "passive"))
      (node (ref "C59") (pin "2") (pinfunction "2_2") (pintype "passive"))
      (node (ref "C6") (pin "2") (pinfunction "2_2") (pintype "passive"))
      (node (ref "C60") (pin "2") (pinfunction "2_2") (pintype "passive"))
      (node (ref "C7") (pin "2") (pinfunction "2_2") (pintype "passive"))
      (node (ref "C8") (pin "2") (pinfunction "2_2") (pintype "passive"))
      (node (ref "C9") (pin "2") (pinfunction "2_2") (pintype "passive"))
      (node (ref "R10") (pin "2") (pinfunction "2_2") (pintype "passive"))
      (node (ref "R12") (pin "1") (pinfunction "1_1") (pintype "passive"))
      (node (ref "R4") (pin "1") (pinfunction "1_1") (pintype "passive"))
      (node (ref "R5") (pin "1") (pinfunction "1_1") (pintype "passive"))
      (node (ref "R6") (pin "1") (pinfunction "1_1") (pintype "passive"))
      (node (ref "R7") (pin "1") (pinfunction "1_1") (pintype "passive"))
      (node (ref "R8") (pin "1") (pinfunction "1_1") (pintype "passive"))
      (node (ref "R9") (pin "1") (pinfunction "1_1") (pintype "passive"))
      (node (ref "U2") (pin "A9") (pinfunction "VSS1_A9") (pintype "power_in"))
      (node (ref "U2") (pin "B1") (pinfunction "VSSQ1_B1") (pintype "power_in"))
      (node (ref "U2") (pin "B3") (pinfunction "VSS2_B3") (pintype "power_in"))
      (node (ref "U2") (pin "B9") (pinfunction "VSSQ2_B9") (pintype "power_in"))
      (node (ref "U2") (pin "D1") (pinfunction "VSSQ3_D1") (pintype "power_in"))
      (node (ref "U2") (pin "D8") (pinfunction "VSSQ4_D8") (pintype "power_in"))
      (node (ref "U2") (pin "E1") (pinfunction "VSS3_E1") (pintype "power_in"))
      (node (ref "U2") (pin "E2") (pinfunction "VSSQ5_E2") (pintype "power_in"))
      (node (ref "U2") (pin "E8") (pinfunction "VSSQ6_E8") (pintype "power_in"))
      (node (ref "U2") (pin "F9") (pinfunction "VSSQ7_F9") (pintype "power_in"))
      (node (ref "U2") (pin "G1") (pinfunction "VSSQ8_G1") (pintype "power_in"))
      (node (ref "U2") (pin "G8") (pinfunction "VSS4_G8") (pintype "power_in"))
      (node (ref "U2") (pin "G9") (pinfunction "VSSQ9_G9") (pintype "power_in"))
      (node (ref "U2") (pin "J2") (pinfunction "VSS5_J2") (pintype "power_in"))
      (node (ref "U2") (pin "J8") (pinfunction "VSS6_J8") (pintype "power_in"))
      (node (ref "U2") (pin "M1") (pinfunction "VSS7_M1") (pintype "power_in"))
      (node (ref "U2") (pin "M9") (pinfunction "VSS8_M9") (pintype "power_in"))
      (node (ref "U2") (pin "P1") (pinfunction "VSS9_P1") (pintype "power_in"))
      (node (ref "U2") (pin "P9") (pinfunction "VSS10_P9") (pintype "power_in"))
      (node (ref "U2") (pin "T1") (pinfunction "VSS11_T1") (pintype "power_in"))
      (node (ref "U2") (pin "T9") (pinfunction "VSS12_T9") (pintype "power_in"))
      (node (ref "U3") (pin "A9") (pinfunction "VSS1_A9") (pintype "power_in"))
      (node (ref "U3") (pin "B1") (pinfunction "VSSQ1_B1") (pintype "power_in"))
      (node (ref "U3") (pin "B3") (pinfunction "VSS2_B3") (pintype "power_in"))
      (node (ref "U3") (pin "B9") (pinfunction "VSSQ2_B9") (pintype "power_in"))
      (node (ref "U3") (pin "D1") (pinfunction "VSSQ3_D1") (pintype "power_in"))
      (node (ref "U3") (pin "D8") (pinfunction "VSSQ4_D8") (pintype "power_in"))
      (node (ref "U3") (pin "E1") (pinfunction "VSS3_E1") (pintype "power_in"))
      (node (ref "U3") (pin "E2") (pinfunction "VSSQ5_E2") (pintype "power_in"))
      (node (ref "U3") (pin "E8") (pinfunction "VSSQ6_E8") (pintype "power_in"))
      (node (ref "U3") (pin "F9") (pinfunction "VSSQ7_F9") (pintype "power_in"))
      (node (ref "U3") (pin "G1") (pinfunction "VSSQ8_G1") (pintype "power_in"))
      (node (ref "U3") (pin "G8") (pinfunction "VSS4_G8") (pintype "power_in"))
      (node (ref "U3") (pin "G9") (pinfunction "VSSQ9_G9") (pintype "power_in"))
      (node (ref "U3") (pin "J2") (pinfunction "VSS5_J2") (pintype "power_in"))
      (node (ref "U3") (pin "J8") (pinfunction "VSS6_J8") (pintype "power_in"))
      (node (ref "U3") (pin "M1") (pinfunction "VSS7_M1") (pintype "power_in"))
      (node (ref "U3") (pin "M9") (pinfunction "VSS8_M9") (pintype "power_in"))
      (node (ref "U3") (pin "P1") (pinfunction "VSS9_P1") (pintype "power_in"))
      (node (ref "U3") (pin "P9") (pinfunction "VSS10_P9") (pintype "power_in"))
      (node (ref "U3") (pin "T1") (pinfunction "VSS11_T1") (pintype "power_in"))
      (node (ref "U3") (pin "T9") (pinfunction "VSS12_T9") (pintype "power_in"))
      (node (ref "U4") (pin "A9") (pinfunction "VSS1_A9") (pintype "power_in"))
      (node (ref "U4") (pin "B1") (pinfunction "VSSQ1_B1") (pintype "power_in"))
      (node (ref "U4") (pin "B3") (pinfunction "VSS2_B3") (pintype "power_in"))
      (node (ref "U4") (pin "B9") (pinfunction "VSSQ2_B9") (pintype "power_in"))
      (node (ref "U4") (pin "D1") (pinfunction "VSSQ3_D1") (pintype "power_in"))
      (node (ref "U4") (pin "D8") (pinfunction "VSSQ4_D8") (pintype "power_in"))
      (node (ref "U4") (pin "E1") (pinfunction "VSS3_E1") (pintype "power_in"))
      (node (ref "U4") (pin "E2") (pinfunction "VSSQ5_E2") (pintype "power_in"))
      (node (ref "U4") (pin "E8") (pinfunction "VSSQ6_E8") (pintype "power_in"))
      (node (ref "U4") (pin "F9") (pinfunction "VSSQ7_F9") (pintype "power_in"))
      (node (ref "U4") (pin "G1") (pinfunction "VSSQ8_G1") (pintype "power_in"))
      (node (ref "U4") (pin "G8") (pinfunction "VSS4_G8") (pintype "power_in"))
      (node (ref "U4") (pin "G9") (pinfunction "VSSQ9_G9") (pintype "power_in"))
      (node (ref "U4") (pin "J2") (pinfunction "VSS5_J2") (pintype "power_in"))
      (node (ref "U4") (pin "J8") (pinfunction "VSS6_J8") (pintype "power_in"))
      (node (ref "U4") (pin "M1") (pinfunction "VSS7_M1") (pintype "power_in"))
      (node (ref "U4") (pin "M9") (pinfunction "VSS8_M9") (pintype "power_in"))
      (node (ref "U4") (pin "P1") (pinfunction "VSS9_P1") (pintype "power_in"))
      (node (ref "U4") (pin "P9") (pinfunction "VSS10_P9") (pintype "power_in"))
      (node (ref "U4") (pin "T1") (pinfunction "VSS11_T1") (pintype "power_in"))
      (node (ref "U4") (pin "T9") (pinfunction "VSS12_T9") (pintype "power_in"))
      (node (ref "U5") (pin "A9") (pinfunction "VSS1_A9") (pintype "power_in"))
      (node (ref "U5") (pin "B1") (pinfunction "VSSQ1_B1") (pintype "power_in"))
      (node (ref "U5") (pin "B3") (pinfunction "VSS2_B3") (pintype "power_in"))
      (node (ref "U5") (pin "B9") (pinfunction "VSSQ2_B9") (pintype "power_in"))
      (node (ref "U5") (pin "D1") (pinfunction "VSSQ3_D1") (pintype "power_in"))
      (node (ref "U5") (pin "D8") (pinfunction "VSSQ4_D8") (pintype "power_in"))
      (node (ref "U5") (pin "E1") (pinfunction "VSS3_E1") (pintype "power_in"))
      (node (ref "U5") (pin "E2") (pinfunction "VSSQ5_E2") (pintype "power_in"))
      (node (ref "U5") (pin "E8") (pinfunction "VSSQ6_E8") (pintype "power_in"))
      (node (ref "U5") (pin "F9") (pinfunction "VSSQ7_F9") (pintype "power_in"))
      (node (ref "U5") (pin "G1") (pinfunction "VSSQ8_G1") (pintype "power_in"))
      (node (ref "U5") (pin "G8") (pinfunction "VSS4_G8") (pintype "power_in"))
      (node (ref "U5") (pin "G9") (pinfunction "VSSQ9_G9") (pintype "power_in"))
      (node (ref "U5") (pin "J2") (pinfunction "VSS5_J2") (pintype "power_in"))
      (node (ref "U5") (pin "J8") (pinfunction "VSS6_J8") (pintype "power_in"))
      (node (ref "U5") (pin "M1") (pinfunction "VSS7_M1") (pintype "power_in"))
      (node (ref "U5") (pin "M9") (pinfunction "VSS8_M9") (pintype "power_in"))
      (node (ref "U5") (pin "P1") (pinfunction "VSS9_P1") (pintype "power_in"))
      (node (ref "U5") (pin "P9") (pinfunction "VSS10_P9") (pintype "power_in"))
      (node (ref "U5") (pin "T1") (pinfunction "VSS11_T1") (pintype "power_in"))
      (node (ref "U5") (pin "T9") (pinfunction "VSS12_T9") (pintype "power_in"))
    )
    (net (code "129") (name "unconnected-(U1C-DRAM_CS1-PadAD17)") (class "Default")
      (node (ref "U1") (pin "AD17") (pinfunction "DRAM_CS1_AD17") (pintype "output"))
    )
    (net (code "130") (name "unconnected-(U1C-DRAM_SDCKE1-PadAA11)") (class "Default")
      (node (ref "U1") (pin "AA11") (pinfunction "DRAM_SDCKE1_AA11") (pintype "output"))
    )
    (net (code "131") (name "unconnected-(U1C-DRAM_SDODT1-PadAB17)") (class "Default")
      (node (ref "U1") (pin "AB17") (pinfunction "DRAM_SDODT1_AB17") (pintype "output"))
    )
    (net (code "132") (name "unconnected-(U2-NC_J1-PadJ1)") (class "Default")
      (node (ref "U2") (pin "J1") (pinfunction "NC_J1_J1") (pintype "passive"))
    )
    (net (code "133") (name "unconnected-(U2-NC_J9-PadJ9)") (class "Default")
      (node (ref "U2") (pin "J9") (pinfunction "NC_J9_J9") (pintype "passive"))
    )
    (net (code "134") (name "unconnected-(U2-NC_L1-PadL1)") (class "Default")
      (node (ref "U2") (pin "L1") (pinfunction "NC_L1_L1") (pintype "passive"))
    )
    (net (code "135") (name "unconnected-(U2-NC_L9-PadL9)") (class "Default")
      (node (ref "U2") (pin "L9") (pinfunction "NC_L9_L9") (pintype "passive"))
    )
    (net (code "136") (name "unconnected-(U3-NC_J1-PadJ1)") (class "Default")
      (node (ref "U3") (pin "J1") (pinfunction "NC_J1_J1") (pintype "passive"))
    )
    (net (code "137") (name "unconnected-(U3-NC_J9-PadJ9)") (class "Default")
      (node (ref "U3") (pin "J9") (pinfunction "NC_J9_J9") (pintype "passive"))
    )
    (net (code "138") (name "unconnected-(U3-NC_L1-PadL1)") (class "Default")
      (node (ref "U3") (pin "L1") (pinfunction "NC_L1_L1") (pintype "passive"))
    )
    (net (code "139") (name "unconnected-(U3-NC_L9-PadL9)") (class "Default")
      (node (ref "U3") (pin "L9") (pinfunction "NC_L9_L9") (pintype "passive"))
    )
    (net (code "140") (name "unconnected-(U4-NC_J1-PadJ1)") (class "Default")
      (node (ref "U4") (pin "J1") (pinfunction "NC_J1_J1") (pintype "passive"))
    )
    (net (code "141") (name "unconnected-(U4-NC_J9-PadJ9)") (class "Default")
      (node (ref "U4") (pin "J9") (pinfunction "NC_J9_J9") (pintype "passive"))
    )
    (net (code "142") (name "unconnected-(U4-NC_L1-PadL1)") (class "Default")
      (node (ref "U4") (pin "L1") (pinfunction "NC_L1_L1") (pintype "passive"))
    )
    (net (code "143") (name "unconnected-(U4-NC_L9-PadL9)") (class "Default")
      (node (ref "U4") (pin "L9") (pinfunction "NC_L9_L9") (pintype "passive"))
    )
    (net (code "144") (name "unconnected-(U5-NC_J1-PadJ1)") (class "Default")
      (node (ref "U5") (pin "J1") (pinfunction "NC_J1_J1") (pintype "passive"))
    )
    (net (code "145") (name "unconnected-(U5-NC_J9-PadJ9)") (class "Default")
      (node (ref "U5") (pin "J9") (pinfunction "NC_J9_J9") (pintype "passive"))
    )
    (net (code "146") (name "unconnected-(U5-NC_L1-PadL1)") (class "Default")
      (node (ref "U5") (pin "L1") (pinfunction "NC_L1_L1") (pintype "passive"))
    )
    (net (code "147") (name "unconnected-(U5-NC_L9-PadL9)") (class "Default")
      (node (ref "U5") (pin "L9") (pinfunction "NC_L9_L9") (pintype "passive"))
    )
  )
)
